# Goldfish_BigBoard_2.net
KiCad netlist of a schematic drawn in EAGLE
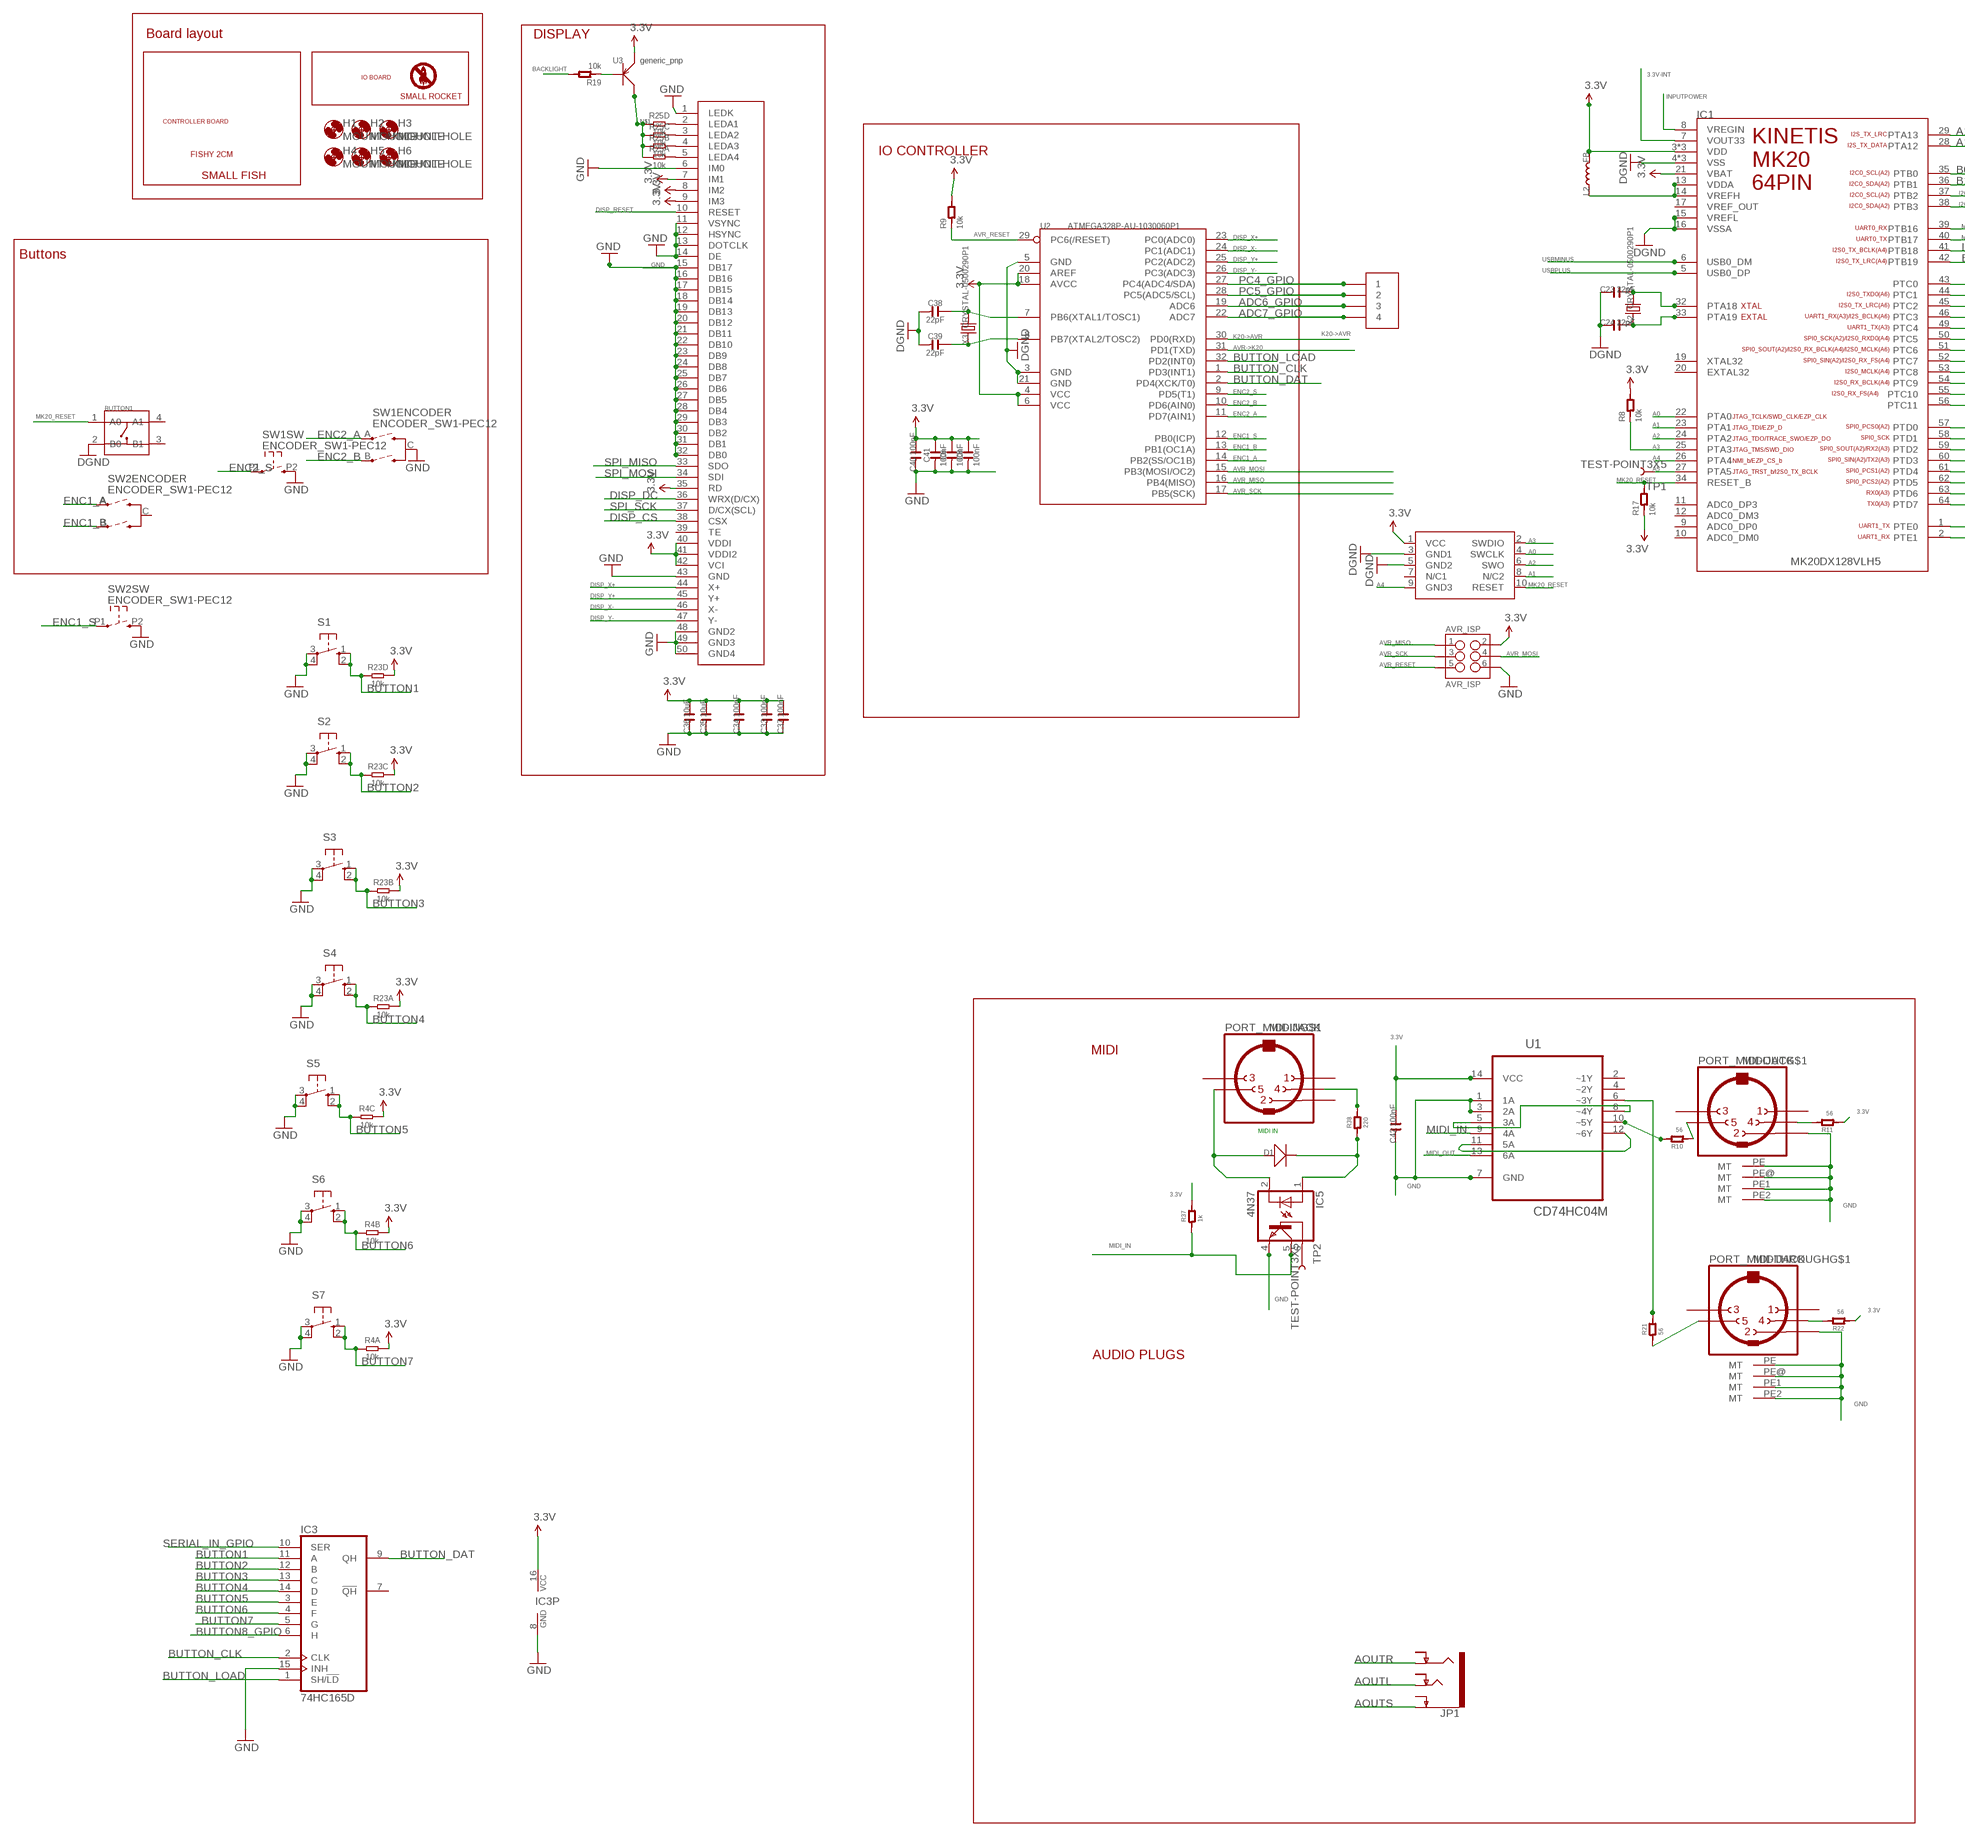
[diagram p0: schematic, sheet 1, part 1 of 3]
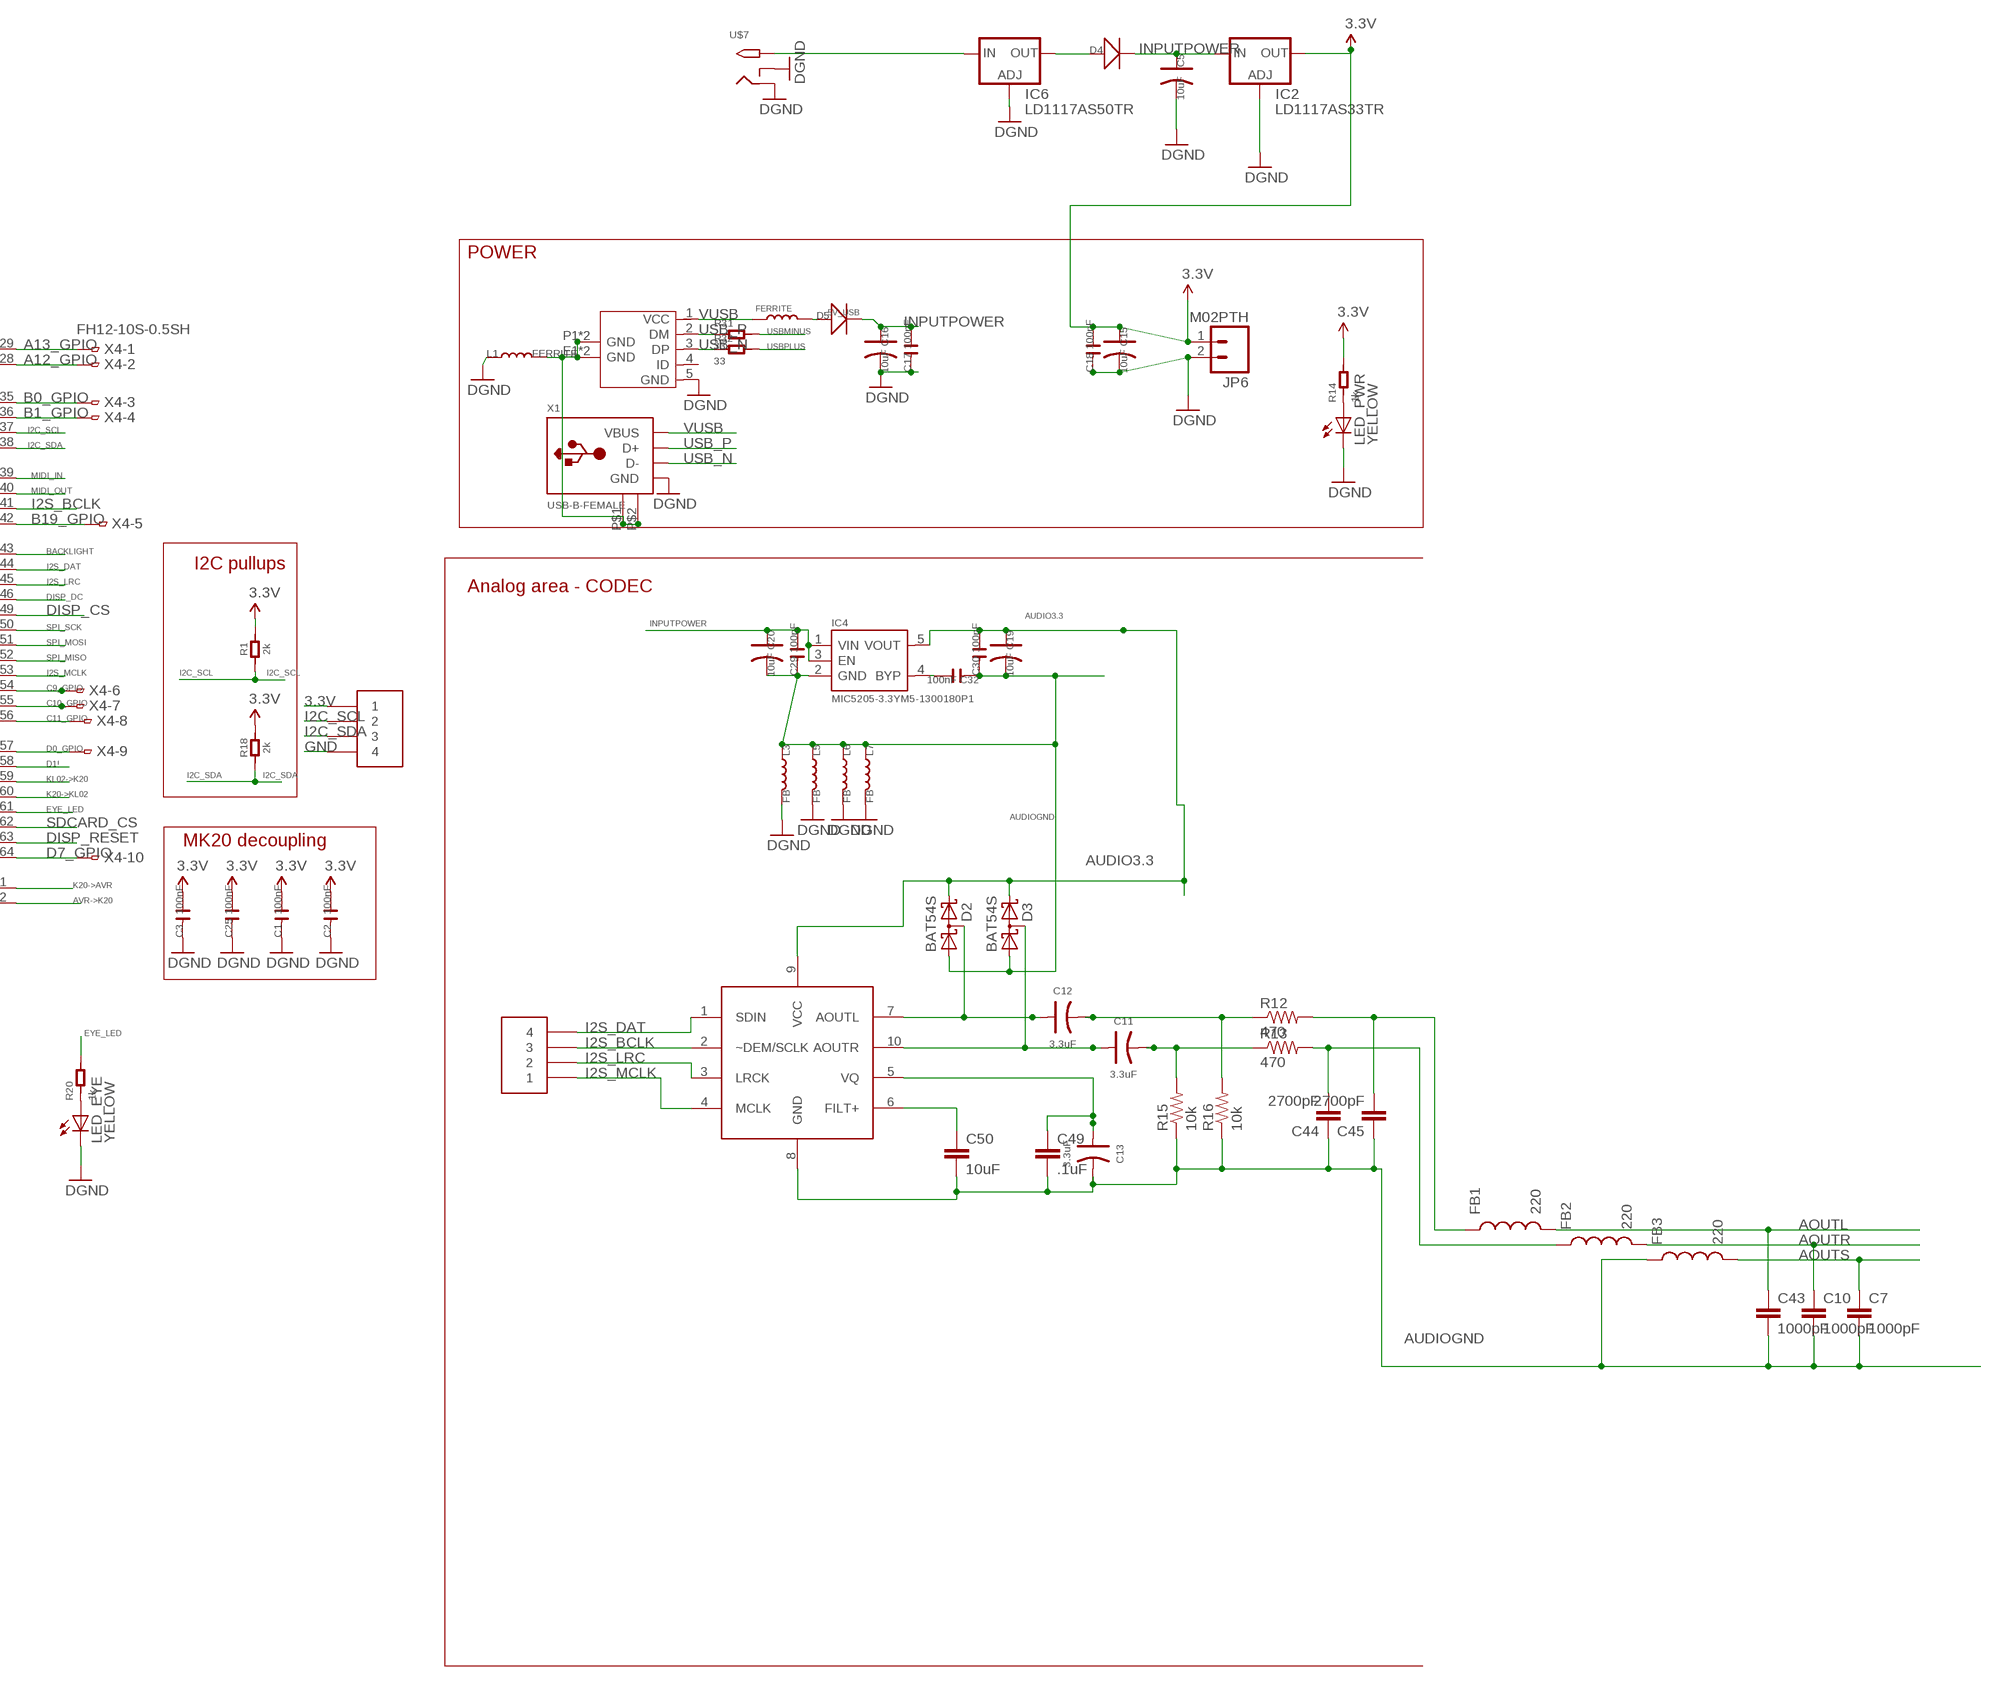
[diagram p1: schematic, sheet 1, part 2 of 3]
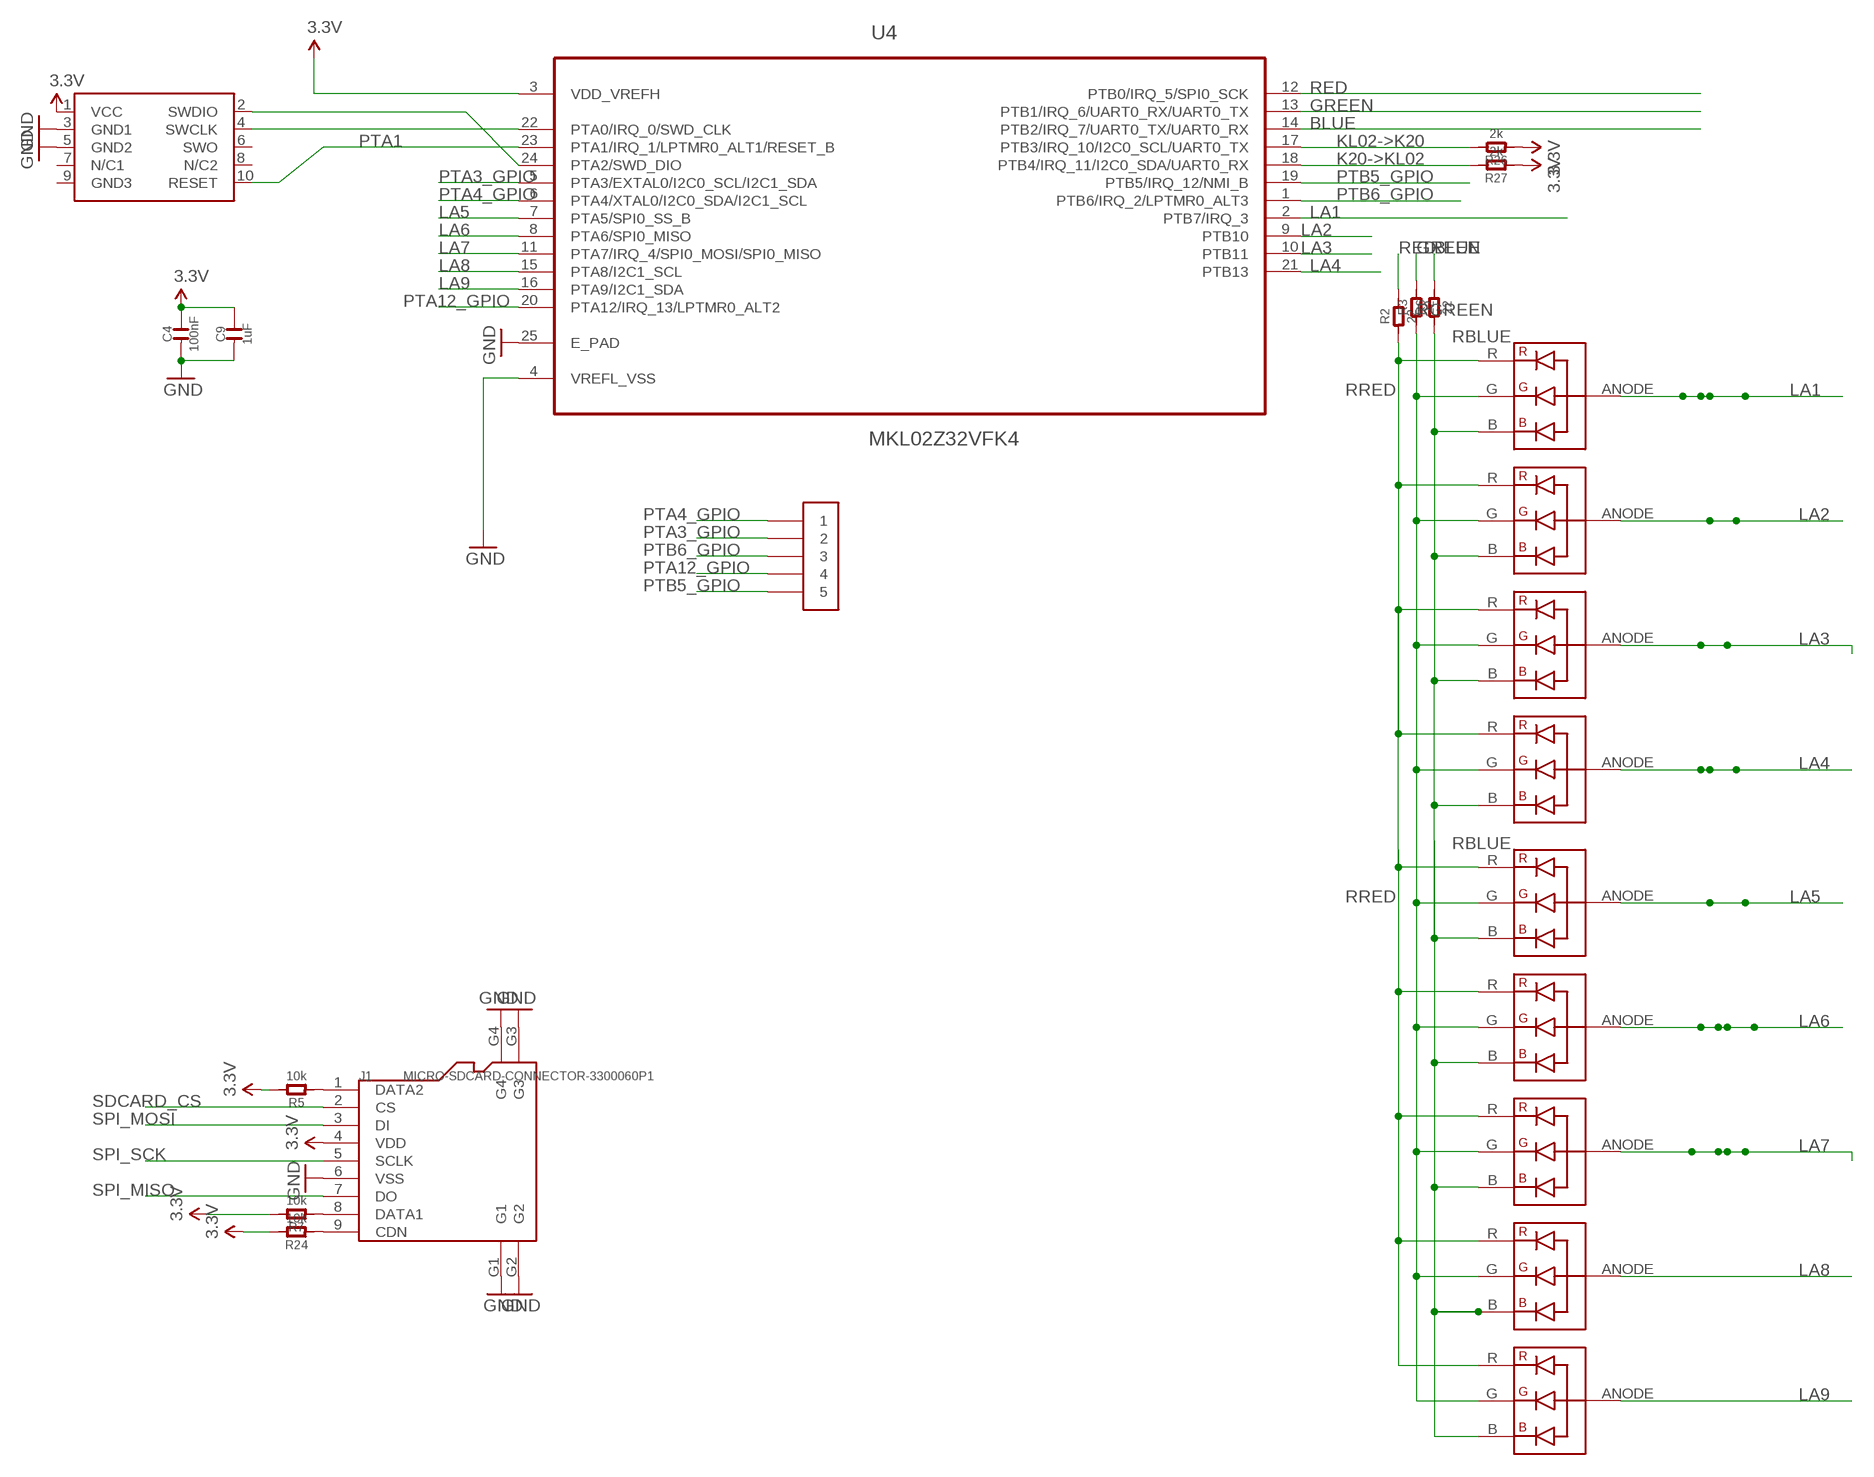
[diagram p2: schematic, sheet 1, part 3 of 3]

(export (version "E")
  (design (tool "Eeschema 10.0.6"))
  (components
    (comp (ref "AVR_ISP")
      (value "AVR_ISP")
      (footprint "eagle-import:2X3_SMT_POSTS")
      (libsource (lib "eagle-import") (part "M03X2SMT"))
    )
    (comp (ref "BUTTON1")
      (value "BUTTON-4P-3100010P1")
      (footprint "eagle-import:4P-SMD-6.0X6.0X5.0H")
      (libsource (lib "eagle-import") (part "BUTTON-4P-3100010P1"))
    )
    (comp (ref "C1")
      (value "100nF")
      (footprint "eagle-import:C0603")
      (libsource (lib "eagle-import") (part "OPL Eagle Library_C-0603"))
    )
    (comp (ref "C2")
      (value "100nF")
      (footprint "eagle-import:C0603")
      (libsource (lib "eagle-import") (part "OPL Eagle Library_C-0603"))
    )
    (comp (ref "C3")
      (value "100nF")
      (footprint "eagle-import:C0603")
      (libsource (lib "eagle-import") (part "OPL Eagle Library_C-0603"))
    )
    (comp (ref "C4")
      (value "100nF")
      (footprint "eagle-import:C0603")
      (libsource (lib "eagle-import") (part "C-0603"))
    )
    (comp (ref "C5")
      (value "10uF")
      (footprint "eagle-import:AVX-A")
      (libsource (lib "eagle-import") (part "OPL Eagle Library_C-POLAR-A"))
    )
    (comp (ref "C6")
      (value "100nF")
      (footprint "eagle-import:C0603")
      (libsource (lib "eagle-import") (part "C-0603"))
    )
    (comp (ref "C7")
      (value "1000pF")
      (footprint "eagle-import:0402-CAP")
      (libsource (lib "eagle-import") (part "CAP0402-CAP"))
    )
    (comp (ref "C8")
      (value "100nF")
      (footprint "eagle-import:C0603")
      (libsource (lib "eagle-import") (part "C-0603"))
    )
    (comp (ref "C9")
      (value "1uF")
      (footprint "eagle-import:C0603")
      (libsource (lib "eagle-import") (part "C-0603"))
    )
    (comp (ref "C10")
      (value "1000pF")
      (footprint "eagle-import:0402-CAP")
      (libsource (lib "eagle-import") (part "CAP0402-CAP"))
    )
    (comp (ref "C11")
      (value "3.3uF")
      (footprint "eagle-import:AVX-A")
      (libsource (lib "eagle-import") (part "C-POLAR-A"))
    )
    (comp (ref "C12")
      (value "3.3uF")
      (footprint "eagle-import:AVX-A")
      (libsource (lib "eagle-import") (part "C-POLAR-A"))
    )
    (comp (ref "C13")
      (value "3.3uF")
      (footprint "eagle-import:AVX-A")
      (libsource (lib "eagle-import") (part "C-POLAR-A"))
    )
    (comp (ref "C15")
      (value "10uF")
      (footprint "eagle-import:AVX-A")
      (libsource (lib "eagle-import") (part "OPL Eagle Library_C-POLAR-A"))
    )
    (comp (ref "C16")
      (value "10uF")
      (footprint "eagle-import:AVX-A")
      (libsource (lib "eagle-import") (part "OPL Eagle Library_C-POLAR-A"))
    )
    (comp (ref "C17")
      (value "100nF")
      (footprint "eagle-import:C0603")
      (libsource (lib "eagle-import") (part "OPL Eagle Library_C-0603"))
    )
    (comp (ref "C18")
      (value "100nF")
      (footprint "eagle-import:C0603")
      (libsource (lib "eagle-import") (part "OPL Eagle Library_C-0603"))
    )
    (comp (ref "C19")
      (value "10uF")
      (footprint "eagle-import:AVX-A")
      (libsource (lib "eagle-import") (part "OPL Eagle Library_C-POLAR-A"))
    )
    (comp (ref "C20")
      (value "10uF")
      (footprint "eagle-import:AVX-A")
      (libsource (lib "eagle-import") (part "OPL Eagle Library_C-POLAR-A"))
    )
    (comp (ref "C23")
      (value "22pF")
      (footprint "eagle-import:C0603")
      (libsource (lib "eagle-import") (part "OPL Eagle Library_C-0603"))
    )
    (comp (ref "C24")
      (value "22pF")
      (footprint "eagle-import:C0603")
      (libsource (lib "eagle-import") (part "OPL Eagle Library_C-0603"))
    )
    (comp (ref "C25")
      (value "100nF")
      (footprint "eagle-import:C0603")
      (libsource (lib "eagle-import") (part "OPL Eagle Library_C-0603"))
    )
    (comp (ref "C29")
      (value "100nF")
      (footprint "eagle-import:C0603")
      (libsource (lib "eagle-import") (part "OPL Eagle Library_C-0603"))
    )
    (comp (ref "C30")
      (value "100nF")
      (footprint "eagle-import:C0603")
      (libsource (lib "eagle-import") (part "OPL Eagle Library_C-0603"))
    )
    (comp (ref "C32")
      (value "100nF")
      (footprint "eagle-import:C0603")
      (libsource (lib "eagle-import") (part "OPL Eagle Library_C-0603"))
    )
    (comp (ref "C33")
      (value "100nF")
      (footprint "eagle-import:C0603")
      (libsource (lib "eagle-import") (part "OPL Eagle Library_C-0603"))
    )
    (comp (ref "C34")
      (value "100nF")
      (footprint "eagle-import:C0603")
      (libsource (lib "eagle-import") (part "OPL Eagle Library_C-0603"))
    )
    (comp (ref "C35")
      (value "10uF")
      (footprint "eagle-import:C0603")
      (libsource (lib "eagle-import") (part "OPL Eagle Library_C-0603"))
    )
    (comp (ref "C36")
      (value "10uF")
      (footprint "eagle-import:C0805")
      (libsource (lib "eagle-import") (part "OPL Eagle Library_C-0805"))
    )
    (comp (ref "C37")
      (value "100nF")
      (footprint "eagle-import:C0805")
      (libsource (lib "eagle-import") (part "OPL Eagle Library_C-0805"))
    )
    (comp (ref "C38")
      (value "22pF")
      (footprint "eagle-import:C0603")
      (libsource (lib "eagle-import") (part "C-0603"))
    )
    (comp (ref "C39")
      (value "22pF")
      (footprint "eagle-import:C0603")
      (libsource (lib "eagle-import") (part "C-0603"))
    )
    (comp (ref "C40")
      (value "100nF")
      (footprint "eagle-import:C0603")
      (libsource (lib "eagle-import") (part "OPL Eagle Library_C-0603"))
    )
    (comp (ref "C41")
      (value "100nF")
      (footprint "eagle-import:C0603")
      (libsource (lib "eagle-import") (part "C-0603"))
    )
    (comp (ref "C42")
      (value "100nF")
      (footprint "eagle-import:C0603")
      (libsource (lib "eagle-import") (part "OPL Eagle Library_C-0603"))
    )
    (comp (ref "C43")
      (value "1000pF")
      (footprint "eagle-import:0402-CAP")
      (libsource (lib "eagle-import") (part "CAP0402-CAP"))
    )
    (comp (ref "C44")
      (value "2700pF")
      (footprint "eagle-import:0402-CAP")
      (libsource (lib "eagle-import") (part "CAP0402-CAP"))
    )
    (comp (ref "C45")
      (value "2700pF")
      (footprint "eagle-import:0402-CAP")
      (libsource (lib "eagle-import") (part "CAP0402-CAP"))
    )
    (comp (ref "C49")
      (value ".1uF")
      (footprint "eagle-import:0402-CAP")
      (libsource (lib "eagle-import") (part "CAP0402-CAP"))
    )
    (comp (ref "C50")
      (value "10uF")
      (footprint "eagle-import:0402-CAP")
      (libsource (lib "eagle-import") (part "CAP0402-CAP"))
    )
    (comp (ref "D1")
      (value "D-D1206")
      (footprint "eagle-import:LL-34")
      (libsource (lib "eagle-import") (part "D-D1206"))
    )
    (comp (ref "D2")
      (value "BAT54S")
      (footprint "eagle-import:SOT23")
      (libsource (lib "eagle-import") (part "BAT54S"))
    )
    (comp (ref "D3")
      (value "BAT54S")
      (footprint "eagle-import:SOT23")
      (libsource (lib "eagle-import") (part "BAT54S"))
    )
    (comp (ref "D4")
      (value "D-D1206")
      (footprint "eagle-import:LL-34")
      (libsource (lib "eagle-import") (part "D-D1206"))
    )
    (comp (ref "D5")
      (value "D-D1206")
      (footprint "eagle-import:LL-34")
      (libsource (lib "eagle-import") (part "D-D1206"))
    )
    (comp (ref "FB1")
      (value "220")
      (footprint "eagle-import:0805")
      (libsource (lib "eagle-import") (part "INDUCTOR0805"))
    )
    (comp (ref "FB2")
      (value "220")
      (footprint "eagle-import:0805")
      (libsource (lib "eagle-import") (part "INDUCTOR0805"))
    )
    (comp (ref "FB3")
      (value "220")
      (footprint "eagle-import:0805")
      (libsource (lib "eagle-import") (part "INDUCTOR0805"))
    )
    (comp (ref "H1")
      (value "MOUNT-HOLE")
      (footprint "eagle-import:3.2-NOMARKINGS-SMALLSAFEZONE")
      (libsource (lib "eagle-import") (part "MOUNT-HOLE"))
    )
    (comp (ref "H2")
      (value "MOUNT-HOLE")
      (footprint "eagle-import:3.2-NOMARKINGS-SMALLSAFEZONE")
      (libsource (lib "eagle-import") (part "MOUNT-HOLE"))
    )
    (comp (ref "H3")
      (value "MOUNT-HOLE")
      (footprint "eagle-import:3.2-NOMARKINGS-SMALLSAFEZONE")
      (libsource (lib "eagle-import") (part "MOUNT-HOLE"))
    )
    (comp (ref "H4")
      (value "MOUNT-HOLE")
      (footprint "eagle-import:3.2-NOMARKINGS-SMALLSAFEZONE")
      (libsource (lib "eagle-import") (part "MOUNT-HOLE"))
    )
    (comp (ref "H5")
      (value "MOUNT-HOLE")
      (footprint "eagle-import:3.2-NOMARKINGS-SMALLSAFEZONE")
      (libsource (lib "eagle-import") (part "MOUNT-HOLE"))
    )
    (comp (ref "H6")
      (value "MOUNT-HOLE")
      (footprint "eagle-import:3.2-NOMARKINGS-SMALLSAFEZONE")
      (libsource (lib "eagle-import") (part "MOUNT-HOLE"))
    )
    (comp (ref "IC1")
      (value "MK20DX128VLH5")
      (footprint "eagle-import:MK20DX128VLH5")
      (libsource (lib "eagle-import") (part "MK20DX128VLH5"))
    )
    (comp (ref "IC2")
      (value "LD1117AS33TR")
      (footprint "eagle-import:SOT223")
      (libsource (lib "eagle-import") (part "LD1117A?S33TR"))
    )
    (comp (ref "IC3")
      (value "74HC165D")
      (footprint "eagle-import:SO16")
      (libsource (lib "eagle-import") (part "74165DHC"))
    )
    (comp (ref "IC4")
      (value "MIC5205-3.3YM5-1300180P1")
      (footprint "eagle-import:SOT23-5")
      (libsource (lib "eagle-import") (part "MIC5205-3.3YM5-1300180P1"))
    )
    (comp (ref "IC5")
      (value "4N37")
      (footprint "eagle-import:DIL06")
      (fields (field (name "MF") "FAIRCHILD SEMICONDUCTOR"))
      (libsource (lib "eagle-import") (part "4N37"))
    )
    (comp (ref "IC6")
      (value "LD1117AS50TR")
      (footprint "eagle-import:SOT223")
      (libsource (lib "eagle-import") (part "LD1117A?S50TR"))
    )
    (comp (ref "J1")
      (value "MICRO-SDCARD-CONNECTOR-3300060P1")
      (footprint "eagle-import:9P-SMD-W-RING")
      (libsource (lib "eagle-import") (part "MICRO-SDCARD-CONNECTOR-3300060P1"))
    )
    (comp (ref "J2")
      (value "MICRO-USB-5P-340015001")
      (footprint "eagle-import:B-SMD-5P")
      (libsource (lib "eagle-import") (part "MICRO-USB-5P-340015001"))
    )
    (comp (ref "JP1")
      (value "AUDIO-JACK4-.25-HORIZ-TRS")
      (footprint "eagle-import:AUDIO-JACK-.25-INCH-HORIZ-PTH")
      (libsource (lib "eagle-import") (part "AUDIO-JACK4-.25-HORIZ-TRS"))
    )
    (comp (ref "JP6")
      (value "M02PTH")
      (footprint "eagle-import:1X02")
      (libsource (lib "eagle-import") (part "M02PTH"))
    )
    (comp (ref "L1")
      (value "FERRITE")
      (footprint "eagle-import:L0603")
      (libsource (lib "eagle-import") (part "L-0603"))
    )
    (comp (ref "L2")
      (value "FB")
      (footprint "eagle-import:L0603")
      (libsource (lib "eagle-import") (part "L-0603"))
    )
    (comp (ref "L3")
      (value "FB")
      (footprint "eagle-import:L0603")
      (libsource (lib "eagle-import") (part "L-0603"))
    )
    (comp (ref "L4")
      (value "FERRITE")
      (footprint "eagle-import:L0603")
      (libsource (lib "eagle-import") (part "L-0603"))
    )
    (comp (ref "L5")
      (value "FB")
      (footprint "eagle-import:L0603")
      (libsource (lib "eagle-import") (part "L-0603"))
    )
    (comp (ref "L6")
      (value "FB")
      (footprint "eagle-import:L0603")
      (libsource (lib "eagle-import") (part "L-0603"))
    )
    (comp (ref "L7")
      (value "FB")
      (footprint "eagle-import:L0603")
      (libsource (lib "eagle-import") (part "L-0603"))
    )
    (comp (ref "LED_EYE")
      (value "YELLOW")
      (footprint "eagle-import:CHIP-LED0603")
      (libsource (lib "eagle-import") (part "LEDCHIP-LED0603"))
    )
    (comp (ref "LED_PWR")
      (value "YELLOW")
      (footprint "eagle-import:CHIP-LED0603")
      (libsource (lib "eagle-import") (part "LEDCHIP-LED0603"))
    )
    (comp (ref "PORT_MIDI-IN")
      (value "MIDIJACK")
      (footprint "eagle-import:CP-2350")
      (libsource (lib "eagle-import") (part "MIDIJACK"))
    )
    (comp (ref "PORT_MIDI-OUT")
      (value "MIDIJACK")
      (footprint "eagle-import:CP-2350")
      (libsource (lib "eagle-import") (part "MIDIJACK"))
    )
    (comp (ref "PORT_MIDI-THROUGH")
      (value "MIDIJACK")
      (footprint "eagle-import:CP-2350")
      (libsource (lib "eagle-import") (part "MIDIJACK"))
    )
    (comp (ref "R1")
      (value "2k")
      (footprint "eagle-import:R0603")
      (libsource (lib "eagle-import") (part "R-0603"))
    )
    (comp (ref "R2")
      (value "22")
      (footprint "eagle-import:R0603")
      (libsource (lib "eagle-import") (part "R-0603"))
    )
    (comp (ref "R3")
      (value "22")
      (footprint "eagle-import:R0603")
      (libsource (lib "eagle-import") (part "R-0603"))
    )
    (comp (ref "R4")
      (value "10k")
      (footprint "eagle-import:R1206-8")
      (libsource (lib "eagle-import") (part "R-4R"))
    )
    (comp (ref "R5")
      (value "10k")
      (footprint "eagle-import:R0603")
      (libsource (lib "eagle-import") (part "R-0603"))
    )
    (comp (ref "R6")
      (value "22")
      (footprint "eagle-import:R0603")
      (libsource (lib "eagle-import") (part "R-0603"))
    )
    (comp (ref "R7")
      (value "10k")
      (footprint "eagle-import:R0603")
      (libsource (lib "eagle-import") (part "R-0603"))
    )
    (comp (ref "R8")
      (value "10k")
      (footprint "eagle-import:R0603")
      (libsource (lib "eagle-import") (part "OPL Eagle Library_R-0603"))
    )
    (comp (ref "R9")
      (value "10k")
      (footprint "eagle-import:R0603")
      (libsource (lib "eagle-import") (part "OPL Eagle Library_R-0603"))
    )
    (comp (ref "R10")
      (value "56")
      (footprint "eagle-import:R0603")
      (libsource (lib "eagle-import") (part "OPL Eagle Library_R-0603"))
    )
    (comp (ref "R11")
      (value "56")
      (footprint "eagle-import:R0603")
      (libsource (lib "eagle-import") (part "OPL Eagle Library_R-0603"))
    )
    (comp (ref "R12")
      (value "470")
      (footprint "eagle-import:0603-RES")
      (libsource (lib "eagle-import") (part "RESISTOR0603-RES"))
    )
    (comp (ref "R13")
      (value "470")
      (footprint "eagle-import:0603-RES")
      (libsource (lib "eagle-import") (part "RESISTOR0603-RES"))
    )
    (comp (ref "R14")
      (value "1k")
      (footprint "eagle-import:R0603")
      (libsource (lib "eagle-import") (part "OPL Eagle Library_R-0603"))
    )
    (comp (ref "R15")
      (value "10k")
      (footprint "eagle-import:0603-RES")
      (libsource (lib "eagle-import") (part "RESISTOR0603-RES"))
    )
    (comp (ref "R16")
      (value "10k")
      (footprint "eagle-import:0603-RES")
      (libsource (lib "eagle-import") (part "RESISTOR0603-RES"))
    )
    (comp (ref "R17")
      (value "10k")
      (footprint "eagle-import:R0603")
      (libsource (lib "eagle-import") (part "OPL Eagle Library_R-0603"))
    )
    (comp (ref "R18")
      (value "2k")
      (footprint "eagle-import:R0603")
      (libsource (lib "eagle-import") (part "R-0603"))
    )
    (comp (ref "R19")
      (value "10k")
      (footprint "eagle-import:R0603")
      (libsource (lib "eagle-import") (part "OPL Eagle Library_R-0603"))
    )
    (comp (ref "R20")
      (value "1k")
      (footprint "eagle-import:R0603")
      (libsource (lib "eagle-import") (part "OPL Eagle Library_R-0603"))
    )
    (comp (ref "R21")
      (value "56")
      (footprint "eagle-import:R0603")
      (libsource (lib "eagle-import") (part "OPL Eagle Library_R-0603"))
    )
    (comp (ref "R22")
      (value "56")
      (footprint "eagle-import:R0603")
      (libsource (lib "eagle-import") (part "OPL Eagle Library_R-0603"))
    )
    (comp (ref "R23")
      (value "10k")
      (footprint "eagle-import:R1206-8")
      (libsource (lib "eagle-import") (part "R-4R"))
    )
    (comp (ref "R24")
      (value "10k")
      (footprint "eagle-import:R0603")
      (libsource (lib "eagle-import") (part "R-0603"))
    )
    (comp (ref "R25")
      (value "10k")
      (footprint "eagle-import:R1206-8")
      (libsource (lib "eagle-import") (part "R-4R"))
    )
    (comp (ref "R26")
      (value "2k")
      (footprint "eagle-import:R0603")
      (libsource (lib "eagle-import") (part "R-0603"))
    )
    (comp (ref "R27")
      (value "2k")
      (footprint "eagle-import:R0603")
      (libsource (lib "eagle-import") (part "R-0603"))
    )
    (comp (ref "R31")
      (value "33")
      (footprint "eagle-import:R0603")
      (libsource (lib "eagle-import") (part "OPL Eagle Library_R-0603"))
    )
    (comp (ref "R32")
      (value "33")
      (footprint "eagle-import:R0603")
      (libsource (lib "eagle-import") (part "OPL Eagle Library_R-0603"))
    )
    (comp (ref "R37")
      (value "1k")
      (footprint "eagle-import:R0603")
      (libsource (lib "eagle-import") (part "OPL Eagle Library_R-0603"))
    )
    (comp (ref "R38")
      (value "220")
      (footprint "eagle-import:R0603")
      (libsource (lib "eagle-import") (part "OPL Eagle Library_R-0603"))
    )
    (comp (ref "S1")
      (value "40-XX-ROUND")
      (footprint "eagle-import:B3F-40XX-ROUND")
      (libsource (lib "eagle-import") (part "40-XX-ROUND"))
    )
    (comp (ref "S2")
      (value "40-XX-ROUND")
      (footprint "eagle-import:B3F-40XX-ROUND")
      (libsource (lib "eagle-import") (part "40-XX-ROUND"))
    )
    (comp (ref "S3")
      (value "40-XX-ROUND")
      (footprint "eagle-import:B3F-40XX-ROUND")
      (libsource (lib "eagle-import") (part "40-XX-ROUND"))
    )
    (comp (ref "S4")
      (value "40-XX-ROUND")
      (footprint "eagle-import:B3F-40XX-ROUND")
      (libsource (lib "eagle-import") (part "40-XX-ROUND"))
    )
    (comp (ref "S5")
      (value "40-XX-ROUND")
      (footprint "eagle-import:B3F-40XX-ROUND")
      (libsource (lib "eagle-import") (part "40-XX-ROUND"))
    )
    (comp (ref "S6")
      (value "40-XX-ROUND")
      (footprint "eagle-import:B3F-40XX-ROUND")
      (libsource (lib "eagle-import") (part "40-XX-ROUND"))
    )
    (comp (ref "S7")
      (value "40-XX-ROUND")
      (footprint "eagle-import:B3F-40XX-ROUND")
      (libsource (lib "eagle-import") (part "40-XX-ROUND"))
    )
    (comp (ref "SW1")
      (value "ENCODER_SW1-PEC12")
      (footprint "eagle-import:PEC12_INCREMENTAL_ENCODER")
      (libsource (lib "eagle-import") (part "ENCODER_SW1-PEC12"))
    )
    (comp (ref "SW2")
      (value "ENCODER_SW1-PEC12")
      (footprint "eagle-import:PEC12_INCREMENTAL_ENCODER")
      (libsource (lib "eagle-import") (part "ENCODER_SW1-PEC12"))
    )
    (comp (ref "SWD1")
      (value "CORTEX_SWD")
      (footprint "eagle-import:M50-3600542")
      (libsource (lib "eagle-import") (part "CORTEX_SWD"))
    )
    (comp (ref "SWD2")
      (value "CORTEX_SWD")
      (footprint "eagle-import:M50-3600542")
      (libsource (lib "eagle-import") (part "CORTEX_SWD"))
    )
    (comp (ref "TP1")
      (value "TEST-POINT3X5")
      (footprint "eagle-import:PAD.03X.05")
      (libsource (lib "eagle-import") (part "TEST-POINT3X5"))
    )
    (comp (ref "TP2")
      (value "TEST-POINT3X5")
      (footprint "eagle-import:PAD.03X.05")
      (libsource (lib "eagle-import") (part "TEST-POINT3X5"))
    )
    (comp (ref "U$1")
      (value "2.8\"TFT2.8\"TFT")
      (footprint "eagle-import:2.8_TFT")
      (libsource (lib "eagle-import") (part "2.8{dblquote}TFT2.8{dblquote}TFT"))
    )
    (comp (ref "U$3")
      (value "FISH2CM_SILK")
      (footprint "eagle-import:FISH_WITHSILK")
      (libsource (lib "eagle-import") (part "FISH2CM_SILK"))
    )
    (comp (ref "U$4")
      (value "FISH_SMALL")
      (footprint "eagle-import:FISH_SMALL")
      (libsource (lib "eagle-import") (part "FISH_SMALL"))
    )
    (comp (ref "U$6")
      (value "CS4344-DAC")
      (footprint "eagle-import:TSSOP-10")
      (libsource (lib "eagle-import") (part "CS4344-DAC"))
    )
    (comp (ref "U$7")
      (value "2.1MMJACKTHM")
      (footprint "eagle-import:163-179PH-EX")
      (libsource (lib "eagle-import") (part "2.1MMJACKTHM"))
    )
    (comp (ref "U$8")
      (value "SMALLROCKET")
      (footprint "eagle-import:SMALLROCKET")
      (libsource (lib "eagle-import") (part "SMALLROCKET"))
    )
    (comp (ref "U$9")
      (value "RGBLED_COMMONANODE")
      (footprint "eagle-import:3.5X2.8_RGB_LED")
      (libsource (lib "eagle-import") (part "RGBLED_COMMONANODE"))
    )
    (comp (ref "U$10")
      (value "RGBLED_COMMONANODE")
      (footprint "eagle-import:3.5X2.8_RGB_LED")
      (libsource (lib "eagle-import") (part "RGBLED_COMMONANODE"))
    )
    (comp (ref "U$11")
      (value "M05")
      (footprint "eagle-import:M05")
      (libsource (lib "eagle-import") (part "M05"))
    )
    (comp (ref "U$12")
      (value "RGBLED_COMMONANODE")
      (footprint "eagle-import:3.5X2.8_RGB_LED")
      (libsource (lib "eagle-import") (part "RGBLED_COMMONANODE"))
    )
    (comp (ref "U$13")
      (value "RGBLED_COMMONANODE")
      (footprint "eagle-import:3.5X2.8_RGB_LED")
      (libsource (lib "eagle-import") (part "RGBLED_COMMONANODE"))
    )
    (comp (ref "U$14")
      (value "RGBLED_COMMONANODE")
      (footprint "eagle-import:3.5X2.8_RGB_LED")
      (libsource (lib "eagle-import") (part "RGBLED_COMMONANODE"))
    )
    (comp (ref "U$15")
      (value "RGBLED_COMMONANODE")
      (footprint "eagle-import:3.5X2.8_RGB_LED")
      (libsource (lib "eagle-import") (part "RGBLED_COMMONANODE"))
    )
    (comp (ref "U$16")
      (value "RGBLED_COMMONANODE")
      (footprint "eagle-import:3.5X2.8_RGB_LED")
      (libsource (lib "eagle-import") (part "RGBLED_COMMONANODE"))
    )
    (comp (ref "U$17")
      (value "RGBLED_COMMONANODE")
      (footprint "eagle-import:3.5X2.8_RGB_LED")
      (libsource (lib "eagle-import") (part "RGBLED_COMMONANODE"))
    )
    (comp (ref "U$18")
      (value "RGBLED_COMMONANODE")
      (footprint "eagle-import:3.5X2.8_RGB_LED")
      (libsource (lib "eagle-import") (part "RGBLED_COMMONANODE"))
    )
    (comp (ref "U$20")
      (value "M04")
      (footprint "eagle-import:M04")
      (libsource (lib "eagle-import") (part "M04"))
    )
    (comp (ref "U$21")
      (value "M04")
      (footprint "eagle-import:M04")
      (libsource (lib "eagle-import") (part "M04"))
    )
    (comp (ref "U$22")
      (value "M04")
      (footprint "eagle-import:M04")
      (libsource (lib "eagle-import") (part "M04"))
    )
    (comp (ref "U1")
      (value "CD74HC04M")
      (footprint "eagle-import:SOIC127P600X175-14N")
      (libsource (lib "eagle-import") (part "CD74HC04M"))
    )
    (comp (ref "U2")
      (value "ATMEGA328P-AU-1030060P1")
      (footprint "eagle-import:TQFP32")
      (libsource (lib "eagle-import") (part "ATMEGA328P-AU-1030060P1"))
    )
    (comp (ref "U3")
      (value "generic_pnp")
      (footprint "eagle-import:SOT23")
      (libsource (lib "eagle-import") (part "TRANSISTOR-PNP-041003001"))
    )
    (comp (ref "U4")
      (value "MKL02Z32VFK4")
      (footprint "eagle-import:QFN50P400X400X100-25N")
      (libsource (lib "eagle-import") (part "MKL02Z32VFK4"))
    )
    (comp (ref "X1")
      (value "USB-B-FEMALE")
      (footprint "eagle-import:FCI61729")
      (libsource (lib "eagle-import") (part "USB-B-FEMALE"))
    )
    (comp (ref "X2")
      (value "CRYSTAL-0500290P1")
      (footprint "eagle-import:2P-SMD-5.0X3.2")
      (libsource (lib "eagle-import") (part "OPL Eagle Library_CRYSTAL-0500290P1"))
    )
    (comp (ref "X3")
      (value "CRYSTAL-0500290P1")
      (footprint "eagle-import:2P-SMD-5.0X3.2")
      (libsource (lib "eagle-import") (part "CRYSTAL-0500290P1"))
    )
    (comp (ref "X4")
      (value "FH12-10S-0.5SH")
      (footprint "eagle-import:FH12-10S-0.5SH")
      (fields (field (name "MPN") "FH12-10S-0.5SH(55)"))
      (libsource (lib "eagle-import") (part "FH12-10S-0.5SH"))
    )
  )
  (nets
    (net (code "1") (name "/3.3V-INT") (class "Default")
      (node (ref "IC1") (pin "7") (pinfunction "VOUT33_7") (pintype "bidirectional"))
    )
    (net (code "2") (name "/5V_USB") (class "Default")
      (node (ref "D5") (pin "A") (pinfunction "+_A") (pintype "passive"))
      (node (ref "L4") (pin "2") (pinfunction "2_2") (pintype "passive"))
    )
    (net (code "3") (name "/A0") (class "Default")
      (node (ref "IC1") (pin "22") (pinfunction "PTA0_22") (pintype "bidirectional"))
      (node (ref "SWD1") (pin "4") (pinfunction "SWCLK_4") (pintype "bidirectional"))
    )
    (net (code "4") (name "/A1") (class "Default")
      (node (ref "IC1") (pin "23") (pinfunction "PTA1_23") (pintype "bidirectional"))
      (node (ref "SWD1") (pin "8") (pinfunction "N/C2_8") (pintype "bidirectional"))
    )
    (net (code "5") (name "/A2") (class "Default")
      (node (ref "IC1") (pin "24") (pinfunction "PTA2_24") (pintype "bidirectional"))
      (node (ref "SWD1") (pin "6") (pinfunction "SWO_6") (pintype "bidirectional"))
    )
    (net (code "6") (name "/A3") (class "Default")
      (node (ref "IC1") (pin "25") (pinfunction "PTA3_25") (pintype "bidirectional"))
      (node (ref "R8") (pin "1") (pinfunction "1_1") (pintype "bidirectional"))
      (node (ref "SWD1") (pin "2") (pinfunction "SWDIO_2") (pintype "bidirectional"))
    )
    (net (code "7") (name "/A4") (class "Default")
      (node (ref "IC1") (pin "26") (pinfunction "PTA4_26") (pintype "bidirectional"))
      (node (ref "SWD1") (pin "9") (pinfunction "GND3_9") (pintype "bidirectional"))
    )
    (net (code "8") (name "/A5") (class "Default")
      (node (ref "IC1") (pin "27") (pinfunction "PTA5_27") (pintype "bidirectional"))
      (node (ref "TP1") (pin "P$1") (pinfunction "1_P$1") (pintype "bidirectional"))
    )
    (net (code "9") (name "/A12_GPIO") (class "Default")
      (node (ref "IC1") (pin "28") (pinfunction "PTA12_28") (pintype "bidirectional"))
      (node (ref "X4") (pin "2") (pinfunction "1_2") (pintype "passive"))
    )
    (net (code "10") (name "/A13_GPIO") (class "Default")
      (node (ref "IC1") (pin "29") (pinfunction "PTA13_29") (pintype "bidirectional"))
      (node (ref "X4") (pin "1") (pinfunction "1_1") (pintype "passive"))
    )
    (net (code "11") (name "/ADC6_GPIO") (class "Default")
      (node (ref "U$20") (pin "P$3") (pinfunction "3_P$3") (pintype "bidirectional"))
      (node (ref "U2") (pin "19") (pinfunction "ADC6_19") (pintype "bidirectional"))
    )
    (net (code "12") (name "/ADC7_GPIO") (class "Default")
      (node (ref "U$20") (pin "P$4") (pinfunction "4_P$4") (pintype "bidirectional"))
      (node (ref "U2") (pin "22") (pinfunction "ADC7_22") (pintype "bidirectional"))
    )
    (net (code "13") (name "/AOUTL") (class "Default")
      (node (ref "C43") (pin "1") (pinfunction "1_1") (pintype "passive"))
      (node (ref "FB1") (pin "2") (pinfunction "2_2") (pintype "passive"))
      (node (ref "JP1") (pin "P$6") (pinfunction "TIP_P$6") (pintype "bidirectional"))
    )
    (net (code "14") (name "/AOUTR") (class "Default")
      (node (ref "C10") (pin "1") (pinfunction "1_1") (pintype "passive"))
      (node (ref "FB2") (pin "2") (pinfunction "2_2") (pintype "passive"))
      (node (ref "JP1") (pin "P$4") (pinfunction "RING_P$4") (pintype "bidirectional"))
    )
    (net (code "15") (name "/AOUTS") (class "Default")
      (node (ref "C7") (pin "1") (pinfunction "1_1") (pintype "passive"))
      (node (ref "FB3") (pin "2") (pinfunction "2_2") (pintype "passive"))
      (node (ref "JP1") (pin "P$2") (pinfunction "EARTH_P$2") (pintype "bidirectional"))
    )
    (net (code "16") (name "/AUDIO3.3") (class "Default")
      (node (ref "C19") (pin "+") (pinfunction "1_+") (pintype "bidirectional"))
      (node (ref "C30") (pin "2") (pinfunction "2_2") (pintype "bidirectional"))
      (node (ref "D2") (pin "2") (pinfunction "C2_2") (pintype "passive"))
      (node (ref "D3") (pin "2") (pinfunction "C2_2") (pintype "passive"))
      (node (ref "IC4") (pin "5") (pinfunction "VOUT_5") (pintype "bidirectional"))
      (node (ref "U$6") (pin "9") (pinfunction "VCC_9") (pintype "bidirectional"))
    )
    (net (code "17") (name "/AUDIOGND") (class "Default")
      (node (ref "C10") (pin "2") (pinfunction "2_2") (pintype "passive"))
      (node (ref "C13") (pin "-") (pinfunction "2_-") (pintype "bidirectional"))
      (node (ref "C19") (pin "-") (pinfunction "2_-") (pintype "bidirectional"))
      (node (ref "C20") (pin "-") (pinfunction "2_-") (pintype "bidirectional"))
      (node (ref "C29") (pin "1") (pinfunction "1_1") (pintype "bidirectional"))
      (node (ref "C30") (pin "1") (pinfunction "1_1") (pintype "bidirectional"))
      (node (ref "C32") (pin "1") (pinfunction "1_1") (pintype "bidirectional"))
      (node (ref "C43") (pin "2") (pinfunction "2_2") (pintype "passive"))
      (node (ref "C44") (pin "1") (pinfunction "1_1") (pintype "passive"))
      (node (ref "C45") (pin "1") (pinfunction "1_1") (pintype "passive"))
      (node (ref "C49") (pin "2") (pinfunction "2_2") (pintype "passive"))
      (node (ref "C50") (pin "2") (pinfunction "2_2") (pintype "passive"))
      (node (ref "C7") (pin "2") (pinfunction "2_2") (pintype "passive"))
      (node (ref "D2") (pin "1") (pinfunction "A1_1") (pintype "passive"))
      (node (ref "D3") (pin "1") (pinfunction "A1_1") (pintype "passive"))
      (node (ref "FB3") (pin "1") (pinfunction "1_1") (pintype "passive"))
      (node (ref "IC4") (pin "2") (pinfunction "GND_2") (pintype "bidirectional"))
      (node (ref "L3") (pin "1") (pinfunction "1_1") (pintype "passive"))
      (node (ref "L5") (pin "1") (pinfunction "1_1") (pintype "passive"))
      (node (ref "L6") (pin "1") (pinfunction "1_1") (pintype "passive"))
      (node (ref "L7") (pin "1") (pinfunction "1_1") (pintype "passive"))
      (node (ref "R15") (pin "1") (pinfunction "1_1") (pintype "passive"))
      (node (ref "R16") (pin "1") (pinfunction "1_1") (pintype "passive"))
      (node (ref "U$6") (pin "8") (pinfunction "GND_8") (pintype "bidirectional"))
    )
    (net (code "18") (name "/AVR->K20") (class "Default")
      (node (ref "IC1") (pin "2") (pinfunction "PTE1_2") (pintype "bidirectional"))
      (node (ref "U2") (pin "31") (pinfunction "PD1(TXD)_31") (pintype "bidirectional"))
    )
    (net (code "19") (name "/AVR_MISO") (class "Default")
      (node (ref "AVR_ISP") (pin "1") (pinfunction "1_1") (pintype "bidirectional"))
      (node (ref "U2") (pin "16") (pinfunction "PB4(MISO)_16") (pintype "bidirectional"))
    )
    (net (code "20") (name "/AVR_MOSI") (class "Default")
      (node (ref "AVR_ISP") (pin "4") (pinfunction "4_4") (pintype "bidirectional"))
      (node (ref "U2") (pin "15") (pinfunction "PB3(MOSI/OC2)_15") (pintype "bidirectional"))
    )
    (net (code "21") (name "/AVR_RESET") (class "Default")
      (node (ref "AVR_ISP") (pin "5") (pinfunction "5_5") (pintype "bidirectional"))
      (node (ref "R9") (pin "1") (pinfunction "1_1") (pintype "bidirectional"))
      (node (ref "U2") (pin "29") (pinfunction "PC6(/RESET)_29") (pintype "bidirectional"))
    )
    (net (code "22") (name "/AVR_SCK") (class "Default")
      (node (ref "AVR_ISP") (pin "3") (pinfunction "3_3") (pintype "bidirectional"))
      (node (ref "U2") (pin "17") (pinfunction "PB5(SCK)_17") (pintype "bidirectional"))
    )
    (net (code "23") (name "/B0_GPIO") (class "Default")
      (node (ref "IC1") (pin "35") (pinfunction "PTB0_35") (pintype "bidirectional"))
      (node (ref "X4") (pin "3") (pinfunction "1_3") (pintype "passive"))
    )
    (net (code "24") (name "/B1_GPIO") (class "Default")
      (node (ref "IC1") (pin "36") (pinfunction "PTB1_36") (pintype "bidirectional"))
      (node (ref "X4") (pin "4") (pinfunction "1_4") (pintype "passive"))
    )
    (net (code "25") (name "/B19_GPIO") (class "Default")
      (node (ref "IC1") (pin "42") (pinfunction "PTB19_42") (pintype "bidirectional"))
      (node (ref "X4") (pin "5") (pinfunction "1_5") (pintype "passive"))
    )
    (net (code "26") (name "/BACKLIGHT") (class "Default")
      (node (ref "IC1") (pin "43") (pinfunction "PTC0_43") (pintype "bidirectional"))
      (node (ref "R19") (pin "2") (pinfunction "2_2") (pintype "bidirectional"))
    )
    (net (code "27") (name "/BLUE") (class "Default")
      (node (ref "R6") (pin "2") (pinfunction "2_2") (pintype "bidirectional"))
      (node (ref "U4") (pin "14") (pinfunction "PTB2/IRQ_7/UART0_TX/UART0_RX_14") (pintype "bidirectional"))
    )
    (net (code "28") (name "/BUTTON1") (class "Default")
      (node (ref "IC3") (pin "11") (pinfunction "A_11") (pintype "input"))
      (node (ref "R23") (pin "4") (pinfunction "1_4") (pintype "passive"))
      (node (ref "S1") (pin "1") (pinfunction "S_1") (pintype "passive"))
      (node (ref "S1") (pin "2") (pinfunction "S1_2") (pintype "passive"))
    )
    (net (code "29") (name "/BUTTON2") (class "Default")
      (node (ref "IC3") (pin "12") (pinfunction "B_12") (pintype "input"))
      (node (ref "R23") (pin "3") (pinfunction "1_3") (pintype "passive"))
      (node (ref "S2") (pin "1") (pinfunction "S_1") (pintype "passive"))
      (node (ref "S2") (pin "2") (pinfunction "S1_2") (pintype "passive"))
    )
    (net (code "30") (name "/BUTTON3") (class "Default")
      (node (ref "IC3") (pin "13") (pinfunction "C_13") (pintype "input"))
      (node (ref "R23") (pin "2") (pinfunction "1_2") (pintype "passive"))
      (node (ref "S3") (pin "1") (pinfunction "S_1") (pintype "passive"))
      (node (ref "S3") (pin "2") (pinfunction "S1_2") (pintype "passive"))
    )
    (net (code "31") (name "/BUTTON4") (class "Default")
      (node (ref "IC3") (pin "14") (pinfunction "D_14") (pintype "input"))
      (node (ref "R23") (pin "1") (pinfunction "1_1") (pintype "passive"))
      (node (ref "S4") (pin "1") (pinfunction "S_1") (pintype "passive"))
      (node (ref "S4") (pin "2") (pinfunction "S1_2") (pintype "passive"))
    )
    (net (code "32") (name "/BUTTON5") (class "Default")
      (node (ref "IC3") (pin "3") (pinfunction "E_3") (pintype "input"))
      (node (ref "R4") (pin "3") (pinfunction "1_3") (pintype "passive"))
      (node (ref "S5") (pin "1") (pinfunction "S_1") (pintype "passive"))
      (node (ref "S5") (pin "2") (pinfunction "S1_2") (pintype "passive"))
    )
    (net (code "33") (name "/BUTTON6") (class "Default")
      (node (ref "IC3") (pin "4") (pinfunction "F_4") (pintype "input"))
      (node (ref "R4") (pin "2") (pinfunction "1_2") (pintype "passive"))
      (node (ref "S6") (pin "1") (pinfunction "S_1") (pintype "passive"))
      (node (ref "S6") (pin "2") (pinfunction "S1_2") (pintype "passive"))
    )
    (net (code "34") (name "/BUTTON7") (class "Default")
      (node (ref "IC3") (pin "5") (pinfunction "G_5") (pintype "input"))
      (node (ref "R4") (pin "1") (pinfunction "1_1") (pintype "passive"))
      (node (ref "S7") (pin "1") (pinfunction "S_1") (pintype "passive"))
      (node (ref "S7") (pin "2") (pinfunction "S1_2") (pintype "passive"))
    )
    (net (code "35") (name "/BUTTON8_GPIO") (class "Default")
      (node (ref "IC3") (pin "6") (pinfunction "H_6") (pintype "input"))
    )
    (net (code "36") (name "/BUTTON_CLK") (class "Default")
      (node (ref "IC3") (pin "2") (pinfunction "CLK_2") (pintype "input"))
      (node (ref "U2") (pin "1") (pinfunction "PD3(INT1)_1") (pintype "bidirectional"))
    )
    (net (code "37") (name "/BUTTON_DAT") (class "Default")
      (node (ref "IC3") (pin "9") (pinfunction "QH_9") (pintype "output"))
      (node (ref "U2") (pin "2") (pinfunction "PD4(XCK/T0)_2") (pintype "bidirectional"))
    )
    (net (code "38") (name "/BUTTON_LOAD") (class "Default")
      (node (ref "IC3") (pin "1") (pinfunction "SH/~{LD}_1") (pintype "input"))
      (node (ref "U2") (pin "32") (pinfunction "PD2(INT0)_32") (pintype "bidirectional"))
    )
    (net (code "39") (name "/C9_GPIO") (class "Default")
      (node (ref "IC1") (pin "54") (pinfunction "PTC9_54") (pintype "bidirectional"))
      (node (ref "X4") (pin "6") (pinfunction "1_6") (pintype "passive"))
    )
    (net (code "40") (name "/C10_GPIO") (class "Default")
      (node (ref "IC1") (pin "55") (pinfunction "PTC10_55") (pintype "bidirectional"))
      (node (ref "X4") (pin "7") (pinfunction "1_7") (pintype "passive"))
    )
    (net (code "41") (name "/C11_GPIO") (class "Default")
      (node (ref "IC1") (pin "56") (pinfunction "PTC11_56") (pintype "bidirectional"))
      (node (ref "X4") (pin "8") (pinfunction "1_8") (pintype "passive"))
    )
    (net (code "42") (name "/D0_GPIO") (class "Default")
      (node (ref "IC1") (pin "57") (pinfunction "PTD0_57") (pintype "bidirectional"))
      (node (ref "X4") (pin "9") (pinfunction "1_9") (pintype "passive"))
    )
    (net (code "43") (name "/D1~{}") (class "Default")
      (node (ref "IC1") (pin "58") (pinfunction "PTD1_58") (pintype "bidirectional"))
    )
    (net (code "44") (name "/D7_GPIO") (class "Default")
      (node (ref "IC1") (pin "64") (pinfunction "PTD7_64") (pintype "bidirectional"))
      (node (ref "X4") (pin "10") (pinfunction "1_10") (pintype "passive"))
    )
    (net (code "45") (name "/DISP_CS") (class "Default")
      (node (ref "IC1") (pin "49") (pinfunction "PTC4_49") (pintype "bidirectional"))
      (node (ref "U$1") (pin "38") (pinfunction "CSX_38") (pintype "input"))
    )
    (net (code "46") (name "/DISP_DC") (class "Default")
      (node (ref "IC1") (pin "46") (pinfunction "PTC3_46") (pintype "bidirectional"))
      (node (ref "U$1") (pin "36") (pinfunction "WRX(D/CX)_36") (pintype "input"))
    )
    (net (code "47") (name "/DISP_RESET") (class "Default")
      (node (ref "IC1") (pin "63") (pinfunction "PTD6_63") (pintype "bidirectional"))
      (node (ref "U$1") (pin "10") (pinfunction "RESET_10") (pintype "input"))
    )
    (net (code "48") (name "/DISP_X+") (class "Default")
      (node (ref "U$1") (pin "44") (pinfunction "X+_44") (pintype "output"))
      (node (ref "U2") (pin "23") (pinfunction "PC0(ADC0)_23") (pintype "bidirectional"))
    )
    (net (code "49") (name "/DISP_X-") (class "Default")
      (node (ref "U$1") (pin "46") (pinfunction "X-_46") (pintype "output"))
      (node (ref "U2") (pin "24") (pinfunction "PC1(ADC1)_24") (pintype "bidirectional"))
    )
    (net (code "50") (name "/DISP_Y+") (class "Default")
      (node (ref "U$1") (pin "45") (pinfunction "Y+_45") (pintype "output"))
      (node (ref "U2") (pin "25") (pinfunction "PC2(ADC2)_25") (pintype "bidirectional"))
    )
    (net (code "51") (name "/DISP_Y-") (class "Default")
      (node (ref "U$1") (pin "47") (pinfunction "Y-_47") (pintype "output"))
      (node (ref "U2") (pin "26") (pinfunction "PC3(ADC3)_26") (pintype "bidirectional"))
    )
    (net (code "52") (name "/ENC1_A") (class "Default")
      (node (ref "SW2") (pin "A") (pinfunction "A_A") (pintype "passive"))
      (node (ref "U2") (pin "14") (pinfunction "PB2(SS/OC1B)_14") (pintype "bidirectional"))
    )
    (net (code "53") (name "/ENC1_B") (class "Default")
      (node (ref "SW2") (pin "B") (pinfunction "B_B") (pintype "passive"))
      (node (ref "U2") (pin "13") (pinfunction "PB1(OC1A)_13") (pintype "bidirectional"))
    )
    (net (code "54") (name "/ENC1_S") (class "Default")
      (node (ref "SW2") (pin "P1") (pinfunction "1_P1") (pintype "passive"))
      (node (ref "U2") (pin "12") (pinfunction "PB0(ICP)_12") (pintype "bidirectional"))
    )
    (net (code "55") (name "/ENC2_A") (class "Default")
      (node (ref "SW1") (pin "A") (pinfunction "A_A") (pintype "passive"))
      (node (ref "U2") (pin "11") (pinfunction "PD7(AIN1)_11") (pintype "bidirectional"))
    )
    (net (code "56") (name "/ENC2_B") (class "Default")
      (node (ref "SW1") (pin "B") (pinfunction "B_B") (pintype "passive"))
      (node (ref "U2") (pin "10") (pinfunction "PD6(AIN0)_10") (pintype "bidirectional"))
    )
    (net (code "57") (name "/ENC2_S") (class "Default")
      (node (ref "SW1") (pin "P1") (pinfunction "1_P1") (pintype "passive"))
      (node (ref "U2") (pin "9") (pinfunction "PD5(T1)_9") (pintype "bidirectional"))
    )
    (net (code "58") (name "/EYE_LED") (class "Default")
      (node (ref "IC1") (pin "61") (pinfunction "PTD4_61") (pintype "bidirectional"))
      (node (ref "R20") (pin "2") (pinfunction "2_2") (pintype "bidirectional"))
    )
    (net (code "59") (name "/GREEN") (class "Default")
      (node (ref "R3") (pin "2") (pinfunction "2_2") (pintype "bidirectional"))
      (node (ref "U4") (pin "13") (pinfunction "PTB1/IRQ_6/UART0_RX/UART0_TX_13") (pintype "bidirectional"))
    )
    (net (code "60") (name "/I2C_SCL") (class "Default")
      (node (ref "IC1") (pin "37") (pinfunction "PTB2_37") (pintype "bidirectional"))
      (node (ref "R1") (pin "1") (pinfunction "1_1") (pintype "bidirectional"))
      (node (ref "U$22") (pin "P$2") (pinfunction "2_P$2") (pintype "bidirectional"))
    )
    (net (code "61") (name "/I2C_SDA") (class "Default")
      (node (ref "IC1") (pin "38") (pinfunction "PTB3_38") (pintype "bidirectional"))
      (node (ref "R18") (pin "1") (pinfunction "1_1") (pintype "bidirectional"))
      (node (ref "U$22") (pin "P$3") (pinfunction "3_P$3") (pintype "bidirectional"))
    )
    (net (code "62") (name "/I2S_BCLK") (class "Default")
      (node (ref "IC1") (pin "41") (pinfunction "PTB18_41") (pintype "bidirectional"))
      (node (ref "U$21") (pin "P$3") (pinfunction "3_P$3") (pintype "bidirectional"))
      (node (ref "U$6") (pin "2") (pinfunction "~{DEM/SCLK}_2") (pintype "bidirectional"))
    )
    (net (code "63") (name "/I2S_DAT") (class "Default")
      (node (ref "IC1") (pin "44") (pinfunction "PTC1_44") (pintype "bidirectional"))
      (node (ref "U$21") (pin "P$4") (pinfunction "4_P$4") (pintype "bidirectional"))
      (node (ref "U$6") (pin "1") (pinfunction "SDIN_1") (pintype "bidirectional"))
    )
    (net (code "64") (name "/I2S_LRC") (class "Default")
      (node (ref "IC1") (pin "45") (pinfunction "PTC2_45") (pintype "bidirectional"))
      (node (ref "U$21") (pin "P$2") (pinfunction "2_P$2") (pintype "bidirectional"))
      (node (ref "U$6") (pin "3") (pinfunction "LRCK_3") (pintype "bidirectional"))
    )
    (net (code "65") (name "/I2S_MCLK") (class "Default")
      (node (ref "IC1") (pin "53") (pinfunction "PTC8_53") (pintype "bidirectional"))
      (node (ref "U$21") (pin "P$1") (pinfunction "1_P$1") (pintype "bidirectional"))
      (node (ref "U$6") (pin "4") (pinfunction "MCLK_4") (pintype "bidirectional"))
    )
    (net (code "66") (name "/INPUTPOWER") (class "Default")
      (node (ref "C16") (pin "+") (pinfunction "1_+") (pintype "bidirectional"))
      (node (ref "C17") (pin "2") (pinfunction "2_2") (pintype "bidirectional"))
      (node (ref "C20") (pin "+") (pinfunction "1_+") (pintype "bidirectional"))
      (node (ref "C29") (pin "2") (pinfunction "2_2") (pintype "bidirectional"))
      (node (ref "C5") (pin "+") (pinfunction "1_+") (pintype "bidirectional"))
      (node (ref "D4") (pin "C") (pinfunction "-_C") (pintype "passive"))
      (node (ref "D5") (pin "C") (pinfunction "-_C") (pintype "passive"))
      (node (ref "IC1") (pin "8") (pinfunction "VREGIN_8") (pintype "bidirectional"))
      (node (ref "IC2") (pin "3") (pinfunction "IN_3") (pintype "input"))
      (node (ref "IC4") (pin "1") (pinfunction "VIN_1") (pintype "bidirectional"))
      (node (ref "IC4") (pin "3") (pinfunction "EN_3") (pintype "bidirectional"))
    )
    (net (code "67") (name "/K20->AVR") (class "Default")
      (node (ref "IC1") (pin "1") (pinfunction "PTE0_1") (pintype "bidirectional"))
      (node (ref "U2") (pin "30") (pinfunction "PD0(RXD)_30") (pintype "bidirectional"))
    )
    (net (code "68") (name "/K20->KL02") (class "Default")
      (node (ref "IC1") (pin "60") (pinfunction "PTD3_60") (pintype "bidirectional"))
      (node (ref "R27") (pin "2") (pinfunction "2_2") (pintype "bidirectional"))
      (node (ref "U4") (pin "18") (pinfunction "PTB4/IRQ_11/I2C0_SDA/UART0_RX_18") (pintype "bidirectional"))
    )
    (net (code "69") (name "/KL02->K20") (class "Default")
      (node (ref "IC1") (pin "59") (pinfunction "PTD2_59") (pintype "bidirectional"))
      (node (ref "R26") (pin "2") (pinfunction "2_2") (pintype "bidirectional"))
      (node (ref "U4") (pin "17") (pinfunction "PTB3/IRQ_10/I2C0_SCL/UART0_TX_17") (pintype "bidirectional"))
    )
    (net (code "70") (name "/LA1") (class "Default")
      (node (ref "U$9") (pin "ANODE") (pinfunction "ANODE_ANODE") (pintype "bidirectional"))
      (node (ref "U4") (pin "2") (pinfunction "PTB7/IRQ_3_2") (pintype "bidirectional"))
    )
    (net (code "71") (name "/LA2") (class "Default")
      (node (ref "U$10") (pin "ANODE") (pinfunction "ANODE_ANODE") (pintype "bidirectional"))
      (node (ref "U4") (pin "9") (pinfunction "PTB10_9") (pintype "bidirectional"))
    )
    (net (code "72") (name "/LA3") (class "Default")
      (node (ref "U$12") (pin "ANODE") (pinfunction "ANODE_ANODE") (pintype "bidirectional"))
      (node (ref "U4") (pin "10") (pinfunction "PTB11_10") (pintype "bidirectional"))
    )
    (net (code "73") (name "/LA4") (class "Default")
      (node (ref "U$13") (pin "ANODE") (pinfunction "ANODE_ANODE") (pintype "bidirectional"))
      (node (ref "U4") (pin "21") (pinfunction "PTB13_21") (pintype "bidirectional"))
    )
    (net (code "74") (name "/LA5") (class "Default")
      (node (ref "U$14") (pin "ANODE") (pinfunction "ANODE_ANODE") (pintype "bidirectional"))
      (node (ref "U4") (pin "7") (pinfunction "PTA5/SPI0_SS_B_7") (pintype "bidirectional"))
    )
    (net (code "75") (name "/LA6") (class "Default")
      (node (ref "U$15") (pin "ANODE") (pinfunction "ANODE_ANODE") (pintype "bidirectional"))
      (node (ref "U4") (pin "8") (pinfunction "PTA6/SPI0_MISO_8") (pintype "bidirectional"))
    )
    (net (code "76") (name "/LA7") (class "Default")
      (node (ref "U$16") (pin "ANODE") (pinfunction "ANODE_ANODE") (pintype "bidirectional"))
      (node (ref "U4") (pin "11") (pinfunction "PTA7/IRQ_4/SPI0_MOSI/SPI0_MISO_11") (pintype "bidirectional"))
    )
    (net (code "77") (name "/LA8") (class "Default")
      (node (ref "U$17") (pin "ANODE") (pinfunction "ANODE_ANODE") (pintype "bidirectional"))
      (node (ref "U4") (pin "15") (pinfunction "PTA8/I2C1_SCL_15") (pintype "bidirectional"))
    )
    (net (code "78") (name "/LA9") (class "Default")
      (node (ref "U$18") (pin "ANODE") (pinfunction "ANODE_ANODE") (pintype "bidirectional"))
      (node (ref "U4") (pin "16") (pinfunction "PTA9/I2C1_SDA_16") (pintype "bidirectional"))
    )
    (net (code "79") (name "/MIDI_IN") (class "Default")
      (node (ref "IC1") (pin "39") (pinfunction "PTB16_39") (pintype "bidirectional"))
      (node (ref "IC5") (pin "5") (pinfunction "COL_5") (pintype "passive"))
      (node (ref "R37") (pin "1") (pinfunction "1_1") (pintype "bidirectional"))
      (node (ref "U1") (pin "9") (pinfunction "4A_9") (pintype "input"))
    )
    (net (code "80") (name "/MIDI_OUT") (class "Default")
      (node (ref "IC1") (pin "40") (pinfunction "PTB17_40") (pintype "bidirectional"))
      (node (ref "U1") (pin "13") (pinfunction "6A_13") (pintype "input"))
    )
    (net (code "81") (name "/MK20_RESET") (class "Default")
      (node (ref "BUTTON1") (pin "1") (pinfunction "A0_1") (pintype "bidirectional"))
      (node (ref "IC1") (pin "34") (pinfunction "RESET_B_34") (pintype "bidirectional"))
      (node (ref "R17") (pin "2") (pinfunction "2_2") (pintype "bidirectional"))
      (node (ref "SWD1") (pin "10") (pinfunction "RESET_10") (pintype "bidirectional"))
    )
    (net (code "82") (name "/N$1") (class "Default")
      (node (ref "R25") (pin "1") (pinfunction "1_1") (pintype "passive"))
      (node (ref "R25") (pin "2") (pinfunction "1_2") (pintype "passive"))
      (node (ref "R25") (pin "3") (pinfunction "1_3") (pintype "passive"))
      (node (ref "R25") (pin "4") (pinfunction "1_4") (pintype "passive"))
      (node (ref "U3") (pin "3") (pinfunction "C_3") (pintype "passive"))
    )
    (net (code "83") (name "/PC4_GPIO") (class "Default")
      (node (ref "U$20") (pin "P$1") (pinfunction "1_P$1") (pintype "bidirectional"))
      (node (ref "U2") (pin "27") (pinfunction "PC4(ADC4/SDA)_27") (pintype "bidirectional"))
    )
    (net (code "84") (name "/PC5_GPIO") (class "Default")
      (node (ref "U$20") (pin "P$2") (pinfunction "2_P$2") (pintype "bidirectional"))
      (node (ref "U2") (pin "28") (pinfunction "PC5(ADC5/SCL)_28") (pintype "bidirectional"))
    )
    (net (code "85") (name "/PTA1") (class "Default")
      (node (ref "SWD2") (pin "10") (pinfunction "RESET_10") (pintype "bidirectional"))
      (node (ref "U4") (pin "23") (pinfunction "PTA1/IRQ_1/LPTMR0_ALT1/RESET_B_23") (pintype "bidirectional"))
    )
    (net (code "86") (name "/PTA3_GPIO") (class "Default")
      (node (ref "U$11") (pin "P$2") (pinfunction "2_P$2") (pintype "bidirectional"))
      (node (ref "U4") (pin "5") (pinfunction "PTA3/EXTAL0/I2C0_SCL/I2C1_SDA_5") (pintype "bidirectional"))
    )
    (net (code "87") (name "/PTA4_GPIO") (class "Default")
      (node (ref "U$11") (pin "P$1") (pinfunction "1_P$1") (pintype "bidirectional"))
      (node (ref "U4") (pin "6") (pinfunction "PTA4/XTAL0/I2C0_SDA/I2C1_SCL_6") (pintype "bidirectional"))
    )
    (net (code "88") (name "/PTA12_GPIO") (class "Default")
      (node (ref "U$11") (pin "P$4") (pinfunction "4_P$4") (pintype "bidirectional"))
      (node (ref "U4") (pin "20") (pinfunction "PTA12/IRQ_13/LPTMR0_ALT2_20") (pintype "bidirectional"))
    )
    (net (code "89") (name "/PTB5_GPIO") (class "Default")
      (node (ref "U$11") (pin "P$5") (pinfunction "5_P$5") (pintype "bidirectional"))
      (node (ref "U4") (pin "19") (pinfunction "PTB5/IRQ_12/NMI_B_19") (pintype "bidirectional"))
    )
    (net (code "90") (name "/PTB6_GPIO") (class "Default")
      (node (ref "U$11") (pin "P$3") (pinfunction "3_P$3") (pintype "bidirectional"))
      (node (ref "U4") (pin "1") (pinfunction "PTB6/IRQ_2/LPTMR0_ALT3_1") (pintype "bidirectional"))
    )
    (net (code "91") (name "/RBLUE") (class "Default")
      (node (ref "R6") (pin "1") (pinfunction "1_1") (pintype "bidirectional"))
      (node (ref "U$10") (pin "B") (pinfunction "B_B") (pintype "bidirectional"))
      (node (ref "U$12") (pin "B") (pinfunction "B_B") (pintype "bidirectional"))
      (node (ref "U$13") (pin "B") (pinfunction "B_B") (pintype "bidirectional"))
      (node (ref "U$14") (pin "B") (pinfunction "B_B") (pintype "bidirectional"))
      (node (ref "U$15") (pin "B") (pinfunction "B_B") (pintype "bidirectional"))
      (node (ref "U$16") (pin "B") (pinfunction "B_B") (pintype "bidirectional"))
      (node (ref "U$17") (pin "B") (pinfunction "B_B") (pintype "bidirectional"))
      (node (ref "U$18") (pin "B") (pinfunction "B_B") (pintype "bidirectional"))
      (node (ref "U$9") (pin "B") (pinfunction "B_B") (pintype "bidirectional"))
    )
    (net (code "92") (name "/RED") (class "Default")
      (node (ref "R2") (pin "2") (pinfunction "2_2") (pintype "bidirectional"))
      (node (ref "U4") (pin "12") (pinfunction "PTB0/IRQ_5/SPI0_SCK_12") (pintype "bidirectional"))
    )
    (net (code "93") (name "/RGREEN") (class "Default")
      (node (ref "R3") (pin "1") (pinfunction "1_1") (pintype "bidirectional"))
      (node (ref "U$10") (pin "G") (pinfunction "G_G") (pintype "bidirectional"))
      (node (ref "U$12") (pin "G") (pinfunction "G_G") (pintype "bidirectional"))
      (node (ref "U$13") (pin "G") (pinfunction "G_G") (pintype "bidirectional"))
      (node (ref "U$14") (pin "G") (pinfunction "G_G") (pintype "bidirectional"))
      (node (ref "U$15") (pin "G") (pinfunction "G_G") (pintype "bidirectional"))
      (node (ref "U$16") (pin "G") (pinfunction "G_G") (pintype "bidirectional"))
      (node (ref "U$17") (pin "G") (pinfunction "G_G") (pintype "bidirectional"))
      (node (ref "U$18") (pin "G") (pinfunction "G_G") (pintype "bidirectional"))
      (node (ref "U$9") (pin "G") (pinfunction "G_G") (pintype "bidirectional"))
    )
    (net (code "94") (name "/RRED") (class "Default")
      (node (ref "R2") (pin "1") (pinfunction "1_1") (pintype "bidirectional"))
      (node (ref "U$10") (pin "R") (pinfunction "R_R") (pintype "bidirectional"))
      (node (ref "U$12") (pin "R") (pinfunction "R_R") (pintype "bidirectional"))
      (node (ref "U$13") (pin "R") (pinfunction "R_R") (pintype "bidirectional"))
      (node (ref "U$14") (pin "R") (pinfunction "R_R") (pintype "bidirectional"))
      (node (ref "U$15") (pin "R") (pinfunction "R_R") (pintype "bidirectional"))
      (node (ref "U$16") (pin "R") (pinfunction "R_R") (pintype "bidirectional"))
      (node (ref "U$17") (pin "R") (pinfunction "R_R") (pintype "bidirectional"))
      (node (ref "U$18") (pin "R") (pinfunction "R_R") (pintype "bidirectional"))
      (node (ref "U$9") (pin "R") (pinfunction "R_R") (pintype "bidirectional"))
    )
    (net (code "95") (name "/SDCARD_CS") (class "Default")
      (node (ref "IC1") (pin "62") (pinfunction "PTD5_62") (pintype "bidirectional"))
      (node (ref "J1") (pin "2") (pinfunction "CS_2") (pintype "bidirectional"))
    )
    (net (code "96") (name "/SERIAL_IN_GPIO") (class "Default")
      (node (ref "IC3") (pin "10") (pinfunction "SER_10") (pintype "input"))
    )
    (net (code "97") (name "/SPI_MISO") (class "Default")
      (node (ref "IC1") (pin "52") (pinfunction "PTC7_52") (pintype "bidirectional"))
      (node (ref "J1") (pin "7") (pinfunction "DO_7") (pintype "bidirectional"))
      (node (ref "U$1") (pin "33") (pinfunction "SDO_33") (pintype "output"))
    )
    (net (code "98") (name "/SPI_MOSI") (class "Default")
      (node (ref "IC1") (pin "51") (pinfunction "PTC6_51") (pintype "bidirectional"))
      (node (ref "J1") (pin "3") (pinfunction "DI_3") (pintype "bidirectional"))
      (node (ref "U$1") (pin "34") (pinfunction "SDI_34") (pintype "input"))
    )
    (net (code "99") (name "/SPI_SCK") (class "Default")
      (node (ref "IC1") (pin "50") (pinfunction "PTC5_50") (pintype "bidirectional"))
      (node (ref "J1") (pin "5") (pinfunction "SCLK_5") (pintype "bidirectional"))
      (node (ref "U$1") (pin "37") (pinfunction "D/CX(SCL)_37") (pintype "input"))
    )
    (net (code "100") (name "/USBMINUS") (class "Default")
      (node (ref "IC1") (pin "6") (pinfunction "USB0_DM_6") (pintype "bidirectional"))
      (node (ref "R31") (pin "2") (pinfunction "2_2") (pintype "bidirectional"))
    )
    (net (code "101") (name "/USBPLUS") (class "Default")
      (node (ref "IC1") (pin "5") (pinfunction "USB0_DP_5") (pintype "bidirectional"))
      (node (ref "R32") (pin "2") (pinfunction "2_2") (pintype "bidirectional"))
    )
    (net (code "102") (name "/USB_N") (class "Default")
      (node (ref "J2") (pin "3") (pinfunction "DP_3") (pintype "bidirectional"))
      (node (ref "R32") (pin "1") (pinfunction "1_1") (pintype "bidirectional"))
      (node (ref "X1") (pin "2") (pinfunction "D-_2") (pintype "bidirectional"))
    )
    (net (code "103") (name "/USB_P") (class "Default")
      (node (ref "J2") (pin "2") (pinfunction "DM_2") (pintype "bidirectional"))
      (node (ref "R31") (pin "1") (pinfunction "1_1") (pintype "bidirectional"))
      (node (ref "X1") (pin "3") (pinfunction "D+_3") (pintype "bidirectional"))
    )
    (net (code "104") (name "/VUSB") (class "Default")
      (node (ref "J2") (pin "1") (pinfunction "VCC_1") (pintype "bidirectional"))
      (node (ref "L4") (pin "1") (pinfunction "1_1") (pintype "passive"))
      (node (ref "X1") (pin "1") (pinfunction "VBUS_1") (pintype "power_in"))
    )
    (net (code "105") (name "3.3V") (class "Default")
      (node (ref "AVR_ISP") (pin "2") (pinfunction "2_2") (pintype "bidirectional"))
      (node (ref "C1") (pin "2") (pinfunction "2_2") (pintype "bidirectional"))
      (node (ref "C15") (pin "+") (pinfunction "1_+") (pintype "bidirectional"))
      (node (ref "C18") (pin "2") (pinfunction "2_2") (pintype "bidirectional"))
      (node (ref "C2") (pin "2") (pinfunction "2_2") (pintype "bidirectional"))
      (node (ref "C25") (pin "2") (pinfunction "2_2") (pintype "bidirectional"))
      (node (ref "C3") (pin "2") (pinfunction "2_2") (pintype "bidirectional"))
      (node (ref "C33") (pin "2") (pinfunction "2_2") (pintype "bidirectional"))
      (node (ref "C34") (pin "2") (pinfunction "2_2") (pintype "bidirectional"))
      (node (ref "C35") (pin "2") (pinfunction "2_2") (pintype "bidirectional"))
      (node (ref "C36") (pin "2") (pinfunction "2_2") (pintype "bidirectional"))
      (node (ref "C37") (pin "2") (pinfunction "2_2") (pintype "bidirectional"))
      (node (ref "C4") (pin "2") (pinfunction "2_2") (pintype "bidirectional"))
      (node (ref "C40") (pin "2") (pinfunction "2_2") (pintype "bidirectional"))
      (node (ref "C41") (pin "2") (pinfunction "2_2") (pintype "bidirectional"))
      (node (ref "C42") (pin "2") (pinfunction "2_2") (pintype "bidirectional"))
      (node (ref "C6") (pin "2") (pinfunction "2_2") (pintype "bidirectional"))
      (node (ref "C8") (pin "2") (pinfunction "2_2") (pintype "bidirectional"))
      (node (ref "C9") (pin "2") (pinfunction "2_2") (pintype "bidirectional"))
      (node (ref "IC1") (pin "21") (pinfunction "VBAT_21") (pintype "bidirectional"))
      (node (ref "IC1") (pin "3") (pinfunction "VDD_3") (pintype "bidirectional"))
      (node (ref "IC1") (pin "30") (pinfunction "VDD_30") (pintype "bidirectional"))
      (node (ref "IC1") (pin "48") (pinfunction "VDD_48") (pintype "bidirectional"))
      (node (ref "IC2") (pin "2") (pinfunction "OUT_2") (pintype "passive"))
      (node (ref "IC2") (pin "4") (pinfunction "OUT_4") (pintype "passive"))
      (node (ref "IC3") (pin "16") (pinfunction "VCC_16") (pintype "power_in"))
      (node (ref "J1") (pin "4") (pinfunction "VDD_4") (pintype "bidirectional"))
      (node (ref "JP6") (pin "1") (pinfunction "1_1") (pintype "passive"))
      (node (ref "L2") (pin "2") (pinfunction "2_2") (pintype "passive"))
      (node (ref "R1") (pin "2") (pinfunction "2_2") (pintype "bidirectional"))
      (node (ref "R11") (pin "1") (pinfunction "1_1") (pintype "bidirectional"))
      (node (ref "R14") (pin "2") (pinfunction "2_2") (pintype "bidirectional"))
      (node (ref "R17") (pin "1") (pinfunction "1_1") (pintype "bidirectional"))
      (node (ref "R18") (pin "2") (pinfunction "2_2") (pintype "bidirectional"))
      (node (ref "R22") (pin "1") (pinfunction "1_1") (pintype "bidirectional"))
      (node (ref "R23") (pin "5") (pinfunction "2_5") (pintype "passive"))
      (node (ref "R23") (pin "6") (pinfunction "2_6") (pintype "passive"))
      (node (ref "R23") (pin "7") (pinfunction "2_7") (pintype "passive"))
      (node (ref "R23") (pin "8") (pinfunction "2_8") (pintype "passive"))
      (node (ref "R24") (pin "2") (pinfunction "2_2") (pintype "bidirectional"))
      (node (ref "R26") (pin "1") (pinfunction "1_1") (pintype "bidirectional"))
      (node (ref "R27") (pin "1") (pinfunction "1_1") (pintype "bidirectional"))
      (node (ref "R37") (pin "2") (pinfunction "2_2") (pintype "bidirectional"))
      (node (ref "R4") (pin "6") (pinfunction "2_6") (pintype "passive"))
      (node (ref "R4") (pin "7") (pinfunction "2_7") (pintype "passive"))
      (node (ref "R4") (pin "8") (pinfunction "2_8") (pintype "passive"))
      (node (ref "R5") (pin "2") (pinfunction "2_2") (pintype "bidirectional"))
      (node (ref "R7") (pin "2") (pinfunction "2_2") (pintype "bidirectional"))
      (node (ref "R8") (pin "2") (pinfunction "2_2") (pintype "bidirectional"))
      (node (ref "R9") (pin "2") (pinfunction "2_2") (pintype "bidirectional"))
      (node (ref "SWD1") (pin "1") (pinfunction "VCC_1") (pintype "bidirectional"))
      (node (ref "SWD2") (pin "1") (pinfunction "VCC_1") (pintype "bidirectional"))
      (node (ref "U$1") (pin "35") (pinfunction "RD_35") (pintype "input"))
      (node (ref "U$1") (pin "40") (pinfunction "VDDI_40") (pintype "power_in"))
      (node (ref "U$1") (pin "41") (pinfunction "VDDI2_41") (pintype "power_in"))
      (node (ref "U$1") (pin "42") (pinfunction "VCI_42") (pintype "power_in"))
      (node (ref "U$1") (pin "7") (pinfunction "IM1_7") (pintype "input"))
      (node (ref "U$1") (pin "8") (pinfunction "IM2_8") (pintype "input"))
      (node (ref "U$1") (pin "9") (pinfunction "IM3_9") (pintype "input"))
      (node (ref "U$22") (pin "P$1") (pinfunction "1_P$1") (pintype "bidirectional"))
      (node (ref "U1") (pin "14") (pinfunction "VCC_14") (pintype "power_in"))
      (node (ref "U2") (pin "18") (pinfunction "AVCC_18") (pintype "bidirectional"))
      (node (ref "U2") (pin "20") (pinfunction "AREF_20") (pintype "bidirectional"))
      (node (ref "U2") (pin "4") (pinfunction "VCC_4") (pintype "bidirectional"))
      (node (ref "U2") (pin "6") (pinfunction "VCC_6") (pintype "bidirectional"))
      (node (ref "U3") (pin "2") (pinfunction "E_2") (pintype "passive"))
      (node (ref "U4") (pin "3") (pinfunction "VDD_VREFH_3") (pintype "power_in"))
    )
    (net (code "106") (name "DGND") (class "Default")
      (node (ref "AVR_ISP") (pin "6") (pinfunction "6_6") (pintype "bidirectional"))
      (node (ref "BUTTON1") (pin "2") (pinfunction "B0_2") (pintype "bidirectional"))
      (node (ref "C1") (pin "1") (pinfunction "1_1") (pintype "bidirectional"))
      (node (ref "C15") (pin "-") (pinfunction "2_-") (pintype "bidirectional"))
      (node (ref "C16") (pin "-") (pinfunction "2_-") (pintype "bidirectional"))
      (node (ref "C17") (pin "1") (pinfunction "1_1") (pintype "bidirectional"))
      (node (ref "C18") (pin "1") (pinfunction "1_1") (pintype "bidirectional"))
      (node (ref "C2") (pin "1") (pinfunction "1_1") (pintype "bidirectional"))
      (node (ref "C23") (pin "1") (pinfunction "1_1") (pintype "bidirectional"))
      (node (ref "C24") (pin "1") (pinfunction "1_1") (pintype "bidirectional"))
      (node (ref "C25") (pin "1") (pinfunction "1_1") (pintype "bidirectional"))
      (node (ref "C3") (pin "1") (pinfunction "1_1") (pintype "bidirectional"))
      (node (ref "C33") (pin "1") (pinfunction "1_1") (pintype "bidirectional"))
      (node (ref "C34") (pin "1") (pinfunction "1_1") (pintype "bidirectional"))
      (node (ref "C35") (pin "1") (pinfunction "1_1") (pintype "bidirectional"))
      (node (ref "C36") (pin "1") (pinfunction "1_1") (pintype "bidirectional"))
      (node (ref "C37") (pin "1") (pinfunction "1_1") (pintype "bidirectional"))
      (node (ref "C38") (pin "1") (pinfunction "1_1") (pintype "bidirectional"))
      (node (ref "C39") (pin "1") (pinfunction "1_1") (pintype "bidirectional"))
      (node (ref "C4") (pin "1") (pinfunction "1_1") (pintype "bidirectional"))
      (node (ref "C40") (pin "1") (pinfunction "1_1") (pintype "bidirectional"))
      (node (ref "C41") (pin "1") (pinfunction "1_1") (pintype "bidirectional"))
      (node (ref "C42") (pin "1") (pinfunction "1_1") (pintype "bidirectional"))
      (node (ref "C5") (pin "-") (pinfunction "2_-") (pintype "bidirectional"))
      (node (ref "C6") (pin "1") (pinfunction "1_1") (pintype "bidirectional"))
      (node (ref "C8") (pin "1") (pinfunction "1_1") (pintype "bidirectional"))
      (node (ref "C9") (pin "1") (pinfunction "1_1") (pintype "bidirectional"))
      (node (ref "IC1") (pin "15") (pinfunction "VREFL_15") (pintype "bidirectional"))
      (node (ref "IC1") (pin "16") (pinfunction "VSSA_16") (pintype "bidirectional"))
      (node (ref "IC1") (pin "31") (pinfunction "VSS_31") (pintype "bidirectional"))
      (node (ref "IC1") (pin "4") (pinfunction "VSS_4") (pintype "bidirectional"))
      (node (ref "IC1") (pin "47") (pinfunction "VSS_47") (pintype "bidirectional"))
      (node (ref "IC2") (pin "1") (pinfunction "ADJ_1") (pintype "input"))
      (node (ref "IC3") (pin "15") (pinfunction "INH_15") (pintype "input"))
      (node (ref "IC3") (pin "8") (pinfunction "GND_8") (pintype "power_in"))
      (node (ref "IC5") (pin "4") (pinfunction "EMI_4") (pintype "passive"))
      (node (ref "IC6") (pin "1") (pinfunction "ADJ_1") (pintype "input"))
      (node (ref "J1") (pin "6") (pinfunction "VSS_6") (pintype "bidirectional"))
      (node (ref "J1") (pin "G1") (pinfunction "G1_G1") (pintype "bidirectional"))
      (node (ref "J1") (pin "G2") (pinfunction "G2_G2") (pintype "bidirectional"))
      (node (ref "J1") (pin "G3") (pinfunction "G3_G3") (pintype "bidirectional"))
      (node (ref "J1") (pin "G4") (pinfunction "G4_G4") (pintype "bidirectional"))
      (node (ref "J2") (pin "5") (pinfunction "GND_5") (pintype "bidirectional"))
      (node (ref "JP6") (pin "2") (pinfunction "2_2") (pintype "passive"))
      (node (ref "L1") (pin "1") (pinfunction "1_1") (pintype "passive"))
      (node (ref "L3") (pin "2") (pinfunction "2_2") (pintype "passive"))
      (node (ref "L5") (pin "2") (pinfunction "2_2") (pintype "passive"))
      (node (ref "L6") (pin "2") (pinfunction "2_2") (pintype "passive"))
      (node (ref "L7") (pin "2") (pinfunction "2_2") (pintype "passive"))
      (node (ref "LED_EYE") (pin "C") (pinfunction "C_C") (pintype "passive"))
      (node (ref "LED_PWR") (pin "C") (pinfunction "C_C") (pintype "passive"))
      (node (ref "PORT_MIDI-OUT") (pin "2") (pinfunction "2_2") (pintype "passive"))
      (node (ref "PORT_MIDI-OUT") (pin "PE") (pinfunction "MT_PE") (pintype "passive"))
      (node (ref "PORT_MIDI-OUT") (pin "PE1") (pinfunction "MT_PE1") (pintype "passive"))
      (node (ref "PORT_MIDI-OUT") (pin "PE2") (pinfunction "MT_PE2") (pintype "passive"))
      (node (ref "PORT_MIDI-OUT") (pin "PE@") (pinfunction "MT_PE@") (pintype "passive"))
      (node (ref "PORT_MIDI-THROUGH") (pin "2") (pinfunction "2_2") (pintype "passive"))
      (node (ref "PORT_MIDI-THROUGH") (pin "PE") (pinfunction "MT_PE") (pintype "passive"))
      (node (ref "PORT_MIDI-THROUGH") (pin "PE1") (pinfunction "MT_PE1") (pintype "passive"))
      (node (ref "PORT_MIDI-THROUGH") (pin "PE2") (pinfunction "MT_PE2") (pintype "passive"))
      (node (ref "PORT_MIDI-THROUGH") (pin "PE@") (pinfunction "MT_PE@") (pintype "passive"))
      (node (ref "S1") (pin "3") (pinfunction "P_3") (pintype "passive"))
      (node (ref "S1") (pin "4") (pinfunction "P1_4") (pintype "passive"))
      (node (ref "S2") (pin "3") (pinfunction "P_3") (pintype "passive"))
      (node (ref "S2") (pin "4") (pinfunction "P1_4") (pintype "passive"))
      (node (ref "S3") (pin "3") (pinfunction "P_3") (pintype "passive"))
      (node (ref "S3") (pin "4") (pinfunction "P1_4") (pintype "passive"))
      (node (ref "S4") (pin "3") (pinfunction "P_3") (pintype "passive"))
      (node (ref "S4") (pin "4") (pinfunction "P1_4") (pintype "passive"))
      (node (ref "S5") (pin "3") (pinfunction "P_3") (pintype "passive"))
      (node (ref "S5") (pin "4") (pinfunction "P1_4") (pintype "passive"))
      (node (ref "S6") (pin "3") (pinfunction "P_3") (pintype "passive"))
      (node (ref "S6") (pin "4") (pinfunction "P1_4") (pintype "passive"))
      (node (ref "S7") (pin "3") (pinfunction "P_3") (pintype "passive"))
      (node (ref "S7") (pin "4") (pinfunction "P1_4") (pintype "passive"))
      (node (ref "SW1") (pin "C") (pinfunction "C_C") (pintype "passive"))
      (node (ref "SW1") (pin "P2") (pinfunction "2_P2") (pintype "passive"))
      (node (ref "SW2") (pin "P2") (pinfunction "2_P2") (pintype "passive"))
      (node (ref "SWD1") (pin "3") (pinfunction "GND1_3") (pintype "bidirectional"))
      (node (ref "SWD1") (pin "5") (pinfunction "GND2_5") (pintype "bidirectional"))
      (node (ref "SWD2") (pin "3") (pinfunction "GND1_3") (pintype "bidirectional"))
      (node (ref "SWD2") (pin "5") (pinfunction "GND2_5") (pintype "bidirectional"))
      (node (ref "U$1") (pin "1") (pinfunction "LEDK_1") (pintype "power_in"))
      (node (ref "U$1") (pin "11") (pinfunction "VSYNC_11") (pintype "input"))
      (node (ref "U$1") (pin "12") (pinfunction "HSYNC_12") (pintype "input"))
      (node (ref "U$1") (pin "13") (pinfunction "DOTCLK_13") (pintype "input"))
      (node (ref "U$1") (pin "14") (pinfunction "DE_14") (pintype "bidirectional"))
      (node (ref "U$1") (pin "15") (pinfunction "DB17_15") (pintype "bidirectional"))
      (node (ref "U$1") (pin "16") (pinfunction "DB16_16") (pintype "bidirectional"))
      (node (ref "U$1") (pin "17") (pinfunction "DB15_17") (pintype "bidirectional"))
      (node (ref "U$1") (pin "18") (pinfunction "DB14_18") (pintype "bidirectional"))
      (node (ref "U$1") (pin "19") (pinfunction "DB13_19") (pintype "bidirectional"))
      (node (ref "U$1") (pin "20") (pinfunction "DB12_20") (pintype "bidirectional"))
      (node (ref "U$1") (pin "21") (pinfunction "DB11_21") (pintype "bidirectional"))
      (node (ref "U$1") (pin "22") (pinfunction "DB10_22") (pintype "bidirectional"))
      (node (ref "U$1") (pin "23") (pinfunction "DB9_23") (pintype "bidirectional"))
      (node (ref "U$1") (pin "24") (pinfunction "DB8_24") (pintype "bidirectional"))
      (node (ref "U$1") (pin "25") (pinfunction "DB7_25") (pintype "bidirectional"))
      (node (ref "U$1") (pin "26") (pinfunction "DB6_26") (pintype "bidirectional"))
      (node (ref "U$1") (pin "27") (pinfunction "DB5_27") (pintype "bidirectional"))
      (node (ref "U$1") (pin "28") (pinfunction "DB4_28") (pintype "bidirectional"))
      (node (ref "U$1") (pin "29") (pinfunction "DB3_29") (pintype "bidirectional"))
      (node (ref "U$1") (pin "30") (pinfunction "DB2_30") (pintype "bidirectional"))
      (node (ref "U$1") (pin "31") (pinfunction "DB1_31") (pintype "bidirectional"))
      (node (ref "U$1") (pin "32") (pinfunction "DB0_32") (pintype "bidirectional"))
      (node (ref "U$1") (pin "43") (pinfunction "GND_43") (pintype "power_in"))
      (node (ref "U$1") (pin "48") (pinfunction "GND2_48") (pintype "power_in"))
      (node (ref "U$1") (pin "49") (pinfunction "GND3_49") (pintype "power_in"))
      (node (ref "U$1") (pin "50") (pinfunction "GND4_50") (pintype "power_in"))
      (node (ref "U$1") (pin "6") (pinfunction "IM0_6") (pintype "input"))
      (node (ref "U$22") (pin "P$4") (pinfunction "4_P$4") (pintype "bidirectional"))
      (node (ref "U$7") (pin "RING") (pinfunction "RING_RING") (pintype "bidirectional"))
      (node (ref "U$7") (pin "RING_SW") (pinfunction "RING_SW_RING_SW") (pintype "bidirectional"))
      (node (ref "U1") (pin "1") (pinfunction "1A_1") (pintype "input"))
      (node (ref "U1") (pin "3") (pinfunction "2A_3") (pintype "input"))
      (node (ref "U1") (pin "7") (pinfunction "GND_7") (pintype "passive"))
      (node (ref "U2") (pin "21") (pinfunction "GND_21") (pintype "bidirectional"))
      (node (ref "U2") (pin "3") (pinfunction "GND_3") (pintype "bidirectional"))
      (node (ref "U2") (pin "5") (pinfunction "GND_5") (pintype "bidirectional"))
      (node (ref "U4") (pin "25") (pinfunction "E_PAD_25") (pintype "passive"))
      (node (ref "U4") (pin "4") (pinfunction "VREFL_VSS_4") (pintype "passive"))
      (node (ref "X1") (pin "4") (pinfunction "GND_4") (pintype "power_in"))
    )
    (net (code "107") (name "Net-(C11-1)") (class "Default")
      (node (ref "C11") (pin "+") (pinfunction "1_+") (pintype "bidirectional"))
      (node (ref "D3") (pin "3") (pinfunction "C1A2_3") (pintype "passive"))
      (node (ref "U$6") (pin "10") (pinfunction "AOUTR_10") (pintype "bidirectional"))
    )
    (net (code "108") (name "Net-(C11-2)") (class "Default")
      (node (ref "C11") (pin "-") (pinfunction "2_-") (pintype "bidirectional"))
      (node (ref "R13") (pin "1") (pinfunction "1_1") (pintype "passive"))
      (node (ref "R15") (pin "2") (pinfunction "2_2") (pintype "passive"))
    )
    (net (code "109") (name "Net-(C12-1)") (class "Default")
      (node (ref "C12") (pin "+") (pinfunction "1_+") (pintype "bidirectional"))
      (node (ref "D2") (pin "3") (pinfunction "C1A2_3") (pintype "passive"))
      (node (ref "U$6") (pin "7") (pinfunction "AOUTL_7") (pintype "bidirectional"))
    )
    (net (code "110") (name "Net-(C12-2)") (class "Default")
      (node (ref "C12") (pin "-") (pinfunction "2_-") (pintype "bidirectional"))
      (node (ref "R12") (pin "1") (pinfunction "1_1") (pintype "passive"))
      (node (ref "R16") (pin "2") (pinfunction "2_2") (pintype "passive"))
    )
    (net (code "111") (name "Net-(C13-1)") (class "Default")
      (node (ref "C13") (pin "+") (pinfunction "1_+") (pintype "bidirectional"))
      (node (ref "C49") (pin "1") (pinfunction "1_1") (pintype "passive"))
      (node (ref "U$6") (pin "5") (pinfunction "VQ_5") (pintype "bidirectional"))
    )
    (net (code "112") (name "Net-(C44-Pad2)") (class "Default")
      (node (ref "C44") (pin "2") (pinfunction "2_2") (pintype "passive"))
      (node (ref "FB2") (pin "1") (pinfunction "1_1") (pintype "passive"))
      (node (ref "R13") (pin "2") (pinfunction "2_2") (pintype "passive"))
    )
    (net (code "113") (name "Net-(C45-Pad2)") (class "Default")
      (node (ref "C45") (pin "2") (pinfunction "2_2") (pintype "passive"))
      (node (ref "FB1") (pin "1") (pinfunction "1_1") (pintype "passive"))
      (node (ref "R12") (pin "2") (pinfunction "2_2") (pintype "passive"))
    )
    (net (code "114") (name "Net-(D1-+)") (class "Default")
      (node (ref "D1") (pin "A") (pinfunction "+_A") (pintype "passive"))
      (node (ref "IC5") (pin "2") (pinfunction "C_2") (pintype "passive"))
      (node (ref "PORT_MIDI-IN") (pin "5") (pinfunction "5_5") (pintype "passive"))
    )
    (net (code "115") (name "Net-(D1--)") (class "Default")
      (node (ref "D1") (pin "C") (pinfunction "-_C") (pintype "passive"))
      (node (ref "IC5") (pin "1") (pinfunction "A_1") (pintype "passive"))
      (node (ref "R38") (pin "1") (pinfunction "1_1") (pintype "bidirectional"))
    )
    (net (code "116") (name "Net-(D4-+)") (class "Default")
      (node (ref "D4") (pin "A") (pinfunction "+_A") (pintype "passive"))
      (node (ref "IC6") (pin "2") (pinfunction "OUT_2") (pintype "passive"))
      (node (ref "IC6") (pin "4") (pinfunction "OUT_4") (pintype "passive"))
    )
    (net (code "117") (name "Net-(IC1-PTA18)") (class "Default")
      (node (ref "C23") (pin "2") (pinfunction "2_2") (pintype "bidirectional"))
      (node (ref "IC1") (pin "32") (pinfunction "PTA18_32") (pintype "bidirectional"))
      (node (ref "X2") (pin "2") (pinfunction "2_2") (pintype "passive"))
    )
    (net (code "118") (name "Net-(IC1-PTA19)") (class "Default")
      (node (ref "C24") (pin "2") (pinfunction "2_2") (pintype "bidirectional"))
      (node (ref "IC1") (pin "33") (pinfunction "PTA19_33") (pintype "bidirectional"))
      (node (ref "X2") (pin "1") (pinfunction "1_1") (pintype "passive"))
    )
    (net (code "119") (name "Net-(IC1-VDDA)") (class "Default")
      (node (ref "IC1") (pin "13") (pinfunction "VDDA_13") (pintype "bidirectional"))
      (node (ref "IC1") (pin "14") (pinfunction "VREFH_14") (pintype "bidirectional"))
      (node (ref "L2") (pin "1") (pinfunction "1_1") (pintype "passive"))
    )
    (net (code "120") (name "Net-(IC4-BYP)") (class "Default")
      (node (ref "C32") (pin "2") (pinfunction "2_2") (pintype "bidirectional"))
      (node (ref "IC4") (pin "4") (pinfunction "BYP_4") (pintype "bidirectional"))
    )
    (net (code "121") (name "Net-(IC5-BAS)") (class "Default")
      (node (ref "IC5") (pin "6") (pinfunction "BAS_6") (pintype "passive"))
      (node (ref "TP2") (pin "P$1") (pinfunction "1_P$1") (pintype "bidirectional"))
    )
    (net (code "122") (name "Net-(IC6-IN)") (class "Default")
      (node (ref "IC6") (pin "3") (pinfunction "IN_3") (pintype "input"))
      (node (ref "U$7") (pin "TIP") (pinfunction "TIP_TIP") (pintype "bidirectional"))
    )
    (net (code "123") (name "Net-(J1-CDN)") (class "Default")
      (node (ref "J1") (pin "9") (pinfunction "CDN_9") (pintype "bidirectional"))
      (node (ref "R24") (pin "1") (pinfunction "1_1") (pintype "bidirectional"))
    )
    (net (code "124") (name "Net-(J1-DATA1)") (class "Default")
      (node (ref "J1") (pin "8") (pinfunction "DATA1_8") (pintype "bidirectional"))
      (node (ref "R7") (pin "1") (pinfunction "1_1") (pintype "bidirectional"))
    )
    (net (code "125") (name "Net-(J1-DATA2)") (class "Default")
      (node (ref "J1") (pin "1") (pinfunction "DATA2_1") (pintype "bidirectional"))
      (node (ref "R5") (pin "1") (pinfunction "1_1") (pintype "bidirectional"))
    )
    (net (code "126") (name "Net-(LED_EYE-PadA)") (class "Default")
      (node (ref "LED_EYE") (pin "A") (pinfunction "A_A") (pintype "passive"))
      (node (ref "R20") (pin "1") (pinfunction "1_1") (pintype "bidirectional"))
    )
    (net (code "127") (name "Net-(LED_PWR-PadA)") (class "Default")
      (node (ref "LED_PWR") (pin "A") (pinfunction "A_A") (pintype "passive"))
      (node (ref "R14") (pin "1") (pinfunction "1_1") (pintype "bidirectional"))
    )
    (net (code "128") (name "Net-(PORT_MIDI-IN-Pad4)") (class "Default")
      (node (ref "PORT_MIDI-IN") (pin "4") (pinfunction "4_4") (pintype "passive"))
      (node (ref "R38") (pin "2") (pinfunction "2_2") (pintype "bidirectional"))
    )
    (net (code "129") (name "Net-(PORT_MIDI-OUT-Pad4)") (class "Default")
      (node (ref "PORT_MIDI-OUT") (pin "4") (pinfunction "4_4") (pintype "passive"))
      (node (ref "R11") (pin "2") (pinfunction "2_2") (pintype "bidirectional"))
    )
    (net (code "130") (name "Net-(PORT_MIDI-OUT-Pad5)") (class "Default")
      (node (ref "PORT_MIDI-OUT") (pin "5") (pinfunction "5_5") (pintype "passive"))
      (node (ref "R10") (pin "1") (pinfunction "1_1") (pintype "bidirectional"))
    )
    (net (code "131") (name "Net-(PORT_MIDI-THROUGH-Pad4)") (class "Default")
      (node (ref "PORT_MIDI-THROUGH") (pin "4") (pinfunction "4_4") (pintype "passive"))
      (node (ref "R22") (pin "2") (pinfunction "2_2") (pintype "bidirectional"))
    )
    (net (code "132") (name "Net-(PORT_MIDI-THROUGH-Pad5)") (class "Default")
      (node (ref "PORT_MIDI-THROUGH") (pin "5") (pinfunction "5_5") (pintype "passive"))
      (node (ref "R21") (pin "1") (pinfunction "1_1") (pintype "bidirectional"))
    )
    (net (code "133") (name "Net-(R25A-2)") (class "Default")
      (node (ref "R25") (pin "8") (pinfunction "2_8") (pintype "passive"))
      (node (ref "U$1") (pin "5") (pinfunction "LEDA4_5") (pintype "power_in"))
    )
    (net (code "134") (name "Net-(R25B-2)") (class "Default")
      (node (ref "R25") (pin "7") (pinfunction "2_7") (pintype "passive"))
      (node (ref "U$1") (pin "4") (pinfunction "LEDA3_4") (pintype "power_in"))
    )
    (net (code "135") (name "Net-(R25C-2)") (class "Default")
      (node (ref "R25") (pin "6") (pinfunction "2_6") (pintype "passive"))
      (node (ref "U$1") (pin "3") (pinfunction "LEDA2_3") (pintype "power_in"))
    )
    (net (code "136") (name "Net-(R25D-2)") (class "Default")
      (node (ref "R25") (pin "5") (pinfunction "2_5") (pintype "passive"))
      (node (ref "U$1") (pin "2") (pinfunction "LEDA1_2") (pintype "power_in"))
    )
    (net (code "137") (name "Net-(SWD2-SWCLK)") (class "Default")
      (node (ref "SWD2") (pin "4") (pinfunction "SWCLK_4") (pintype "bidirectional"))
      (node (ref "U4") (pin "22") (pinfunction "PTA0/IRQ_0/SWD_CLK_22") (pintype "bidirectional"))
    )
    (net (code "138") (name "Net-(SWD2-SWDIO)") (class "Default")
      (node (ref "SWD2") (pin "2") (pinfunction "SWDIO_2") (pintype "bidirectional"))
      (node (ref "U4") (pin "24") (pinfunction "PTA2/SWD_DIO_24") (pintype "bidirectional"))
    )
    (net (code "139") (name "Net-(U$6-FILT+)") (class "Default")
      (node (ref "C50") (pin "1") (pinfunction "1_1") (pintype "passive"))
      (node (ref "U$6") (pin "6") (pinfunction "FILT+_6") (pintype "bidirectional"))
    )
    (net (code "140") (name "Net-(U1-3A)") (class "Default")
      (node (ref "U1") (pin "5") (pinfunction "3A_5") (pintype "input"))
      (node (ref "U1") (pin "8") (pinfunction "~{4Y}_8") (pintype "output"))
    )
    (net (code "141") (name "Net-(U1-5A)") (class "Default")
      (node (ref "U1") (pin "11") (pinfunction "5A_11") (pintype "input"))
      (node (ref "U1") (pin "12") (pinfunction "~{6Y}_12") (pintype "output"))
    )
    (net (code "142") (name "Net-(U1-~{3Y})") (class "Default")
      (node (ref "R21") (pin "2") (pinfunction "2_2") (pintype "bidirectional"))
      (node (ref "U1") (pin "6") (pinfunction "~{3Y}_6") (pintype "output"))
    )
    (net (code "143") (name "Net-(U1-~{5Y})") (class "Default")
      (node (ref "R10") (pin "2") (pinfunction "2_2") (pintype "bidirectional"))
      (node (ref "U1") (pin "10") (pinfunction "~{5Y}_10") (pintype "output"))
    )
    (net (code "144") (name "Net-(U2-PB6(XTAL1{slash}TOSC1))") (class "Default")
      (node (ref "C38") (pin "2") (pinfunction "2_2") (pintype "bidirectional"))
      (node (ref "U2") (pin "7") (pinfunction "PB6(XTAL1/TOSC1)_7") (pintype "bidirectional"))
      (node (ref "X3") (pin "2") (pinfunction "2_2") (pintype "passive"))
    )
    (net (code "145") (name "Net-(U2-PB7(XTAL2{slash}TOSC2))") (class "Default")
      (node (ref "C39") (pin "2") (pinfunction "2_2") (pintype "bidirectional"))
      (node (ref "U2") (pin "8") (pinfunction "PB7(XTAL2/TOSC2)_8") (pintype "bidirectional"))
      (node (ref "X3") (pin "1") (pinfunction "1_1") (pintype "passive"))
    )
    (net (code "146") (name "Net-(U3-B)") (class "Default")
      (node (ref "R19") (pin "1") (pinfunction "1_1") (pintype "bidirectional"))
      (node (ref "U3") (pin "1") (pinfunction "B_1") (pintype "passive"))
    )
    (net (code "147") (name "Net-(X1-GND1)") (class "Default")
      (node (ref "J2") (pin "E1") (pinfunction "GND_E1") (pintype "bidirectional"))
      (node (ref "J2") (pin "E2") (pinfunction "GND_E2") (pintype "bidirectional"))
      (node (ref "J2") (pin "P1") (pinfunction "GND_P1") (pintype "bidirectional"))
      (node (ref "J2") (pin "P2") (pinfunction "GND_P2") (pintype "bidirectional"))
      (node (ref "L1") (pin "2") (pinfunction "2_2") (pintype "passive"))
      (node (ref "X1") (pin "P$1") (pinfunction "GND1_P$1") (pintype "power_in"))
      (node (ref "X1") (pin "P$2") (pinfunction "GND2_P$2") (pintype "power_in"))
    )
    (net (code "148") (name "unconnected-(BUTTON1-A1-Pad4)") (class "Default")
      (node (ref "BUTTON1") (pin "4") (pinfunction "A1_4") (pintype "bidirectional"))
    )
    (net (code "149") (name "unconnected-(BUTTON1-B1-Pad3)") (class "Default")
      (node (ref "BUTTON1") (pin "3") (pinfunction "B1_3") (pintype "bidirectional"))
    )
    (net (code "150") (name "unconnected-(IC1-ADC0_DM0-Pad10)") (class "Default")
      (node (ref "IC1") (pin "10") (pinfunction "ADC0_DM0_10") (pintype "bidirectional"))
    )
    (net (code "151") (name "unconnected-(IC1-ADC0_DM3-Pad12)") (class "Default")
      (node (ref "IC1") (pin "12") (pinfunction "ADC0_DM3_12") (pintype "bidirectional"))
    )
    (net (code "152") (name "unconnected-(IC1-ADC0_DP0-Pad9)") (class "Default")
      (node (ref "IC1") (pin "9") (pinfunction "ADC0_DP0_9") (pintype "bidirectional"))
    )
    (net (code "153") (name "unconnected-(IC1-ADC0_DP3-Pad11)") (class "Default")
      (node (ref "IC1") (pin "11") (pinfunction "ADC0_DP3_11") (pintype "bidirectional"))
    )
    (net (code "154") (name "unconnected-(IC1-EXTAL32-Pad20)") (class "Default")
      (node (ref "IC1") (pin "20") (pinfunction "EXTAL32_20") (pintype "bidirectional"))
    )
    (net (code "155") (name "unconnected-(IC1-VREF_OUT-Pad17)") (class "Default")
      (node (ref "IC1") (pin "17") (pinfunction "VREF_OUT_17") (pintype "bidirectional"))
    )
    (net (code "156") (name "unconnected-(IC1-XTAL32-Pad19)") (class "Default")
      (node (ref "IC1") (pin "19") (pinfunction "XTAL32_19") (pintype "bidirectional"))
    )
    (net (code "157") (name "unconnected-(IC3A-~{QH}-Pad7)") (class "Default")
      (node (ref "IC3") (pin "7") (pinfunction "~{QH}_7") (pintype "output"))
    )
    (net (code "158") (name "unconnected-(J2-ID-Pad4)") (class "Default")
      (node (ref "J2") (pin "4") (pinfunction "ID_4") (pintype "bidirectional"))
    )
    (net (code "159") (name "unconnected-(JP1-EARTH-NORM-PadP$3)") (class "Default")
      (node (ref "JP1") (pin "P$3") (pinfunction "EARTH-NORM_P$3") (pintype "bidirectional"))
    )
    (net (code "160") (name "unconnected-(JP1-RING-NORM-PadP$5)") (class "Default")
      (node (ref "JP1") (pin "P$5") (pinfunction "RING-NORM_P$5") (pintype "bidirectional"))
    )
    (net (code "161") (name "unconnected-(JP1-TIP-NORM-PadP$7)") (class "Default")
      (node (ref "JP1") (pin "P$7") (pinfunction "TIP-NORM_P$7") (pintype "bidirectional"))
    )
    (net (code "162") (name "unconnected-(PORT_MIDI-IN-Pad1)") (class "Default")
      (node (ref "PORT_MIDI-IN") (pin "1") (pinfunction "1_1") (pintype "passive"))
    )
    (net (code "163") (name "unconnected-(PORT_MIDI-IN-Pad2)") (class "Default")
      (node (ref "PORT_MIDI-IN") (pin "2") (pinfunction "2_2") (pintype "passive"))
    )
    (net (code "164") (name "unconnected-(PORT_MIDI-IN-Pad3)") (class "Default")
      (node (ref "PORT_MIDI-IN") (pin "3") (pinfunction "3_3") (pintype "passive"))
    )
    (net (code "165") (name "unconnected-(PORT_MIDI-OUT-Pad1)") (class "Default")
      (node (ref "PORT_MIDI-OUT") (pin "1") (pinfunction "1_1") (pintype "passive"))
    )
    (net (code "166") (name "unconnected-(PORT_MIDI-OUT-Pad3)") (class "Default")
      (node (ref "PORT_MIDI-OUT") (pin "3") (pinfunction "3_3") (pintype "passive"))
    )
    (net (code "167") (name "unconnected-(PORT_MIDI-THROUGH-Pad1)") (class "Default")
      (node (ref "PORT_MIDI-THROUGH") (pin "1") (pinfunction "1_1") (pintype "passive"))
    )
    (net (code "168") (name "unconnected-(PORT_MIDI-THROUGH-Pad3)") (class "Default")
      (node (ref "PORT_MIDI-THROUGH") (pin "3") (pinfunction "3_3") (pintype "passive"))
    )
    (net (code "169") (name "unconnected-(SW2-PadC)") (class "Default")
      (node (ref "SW2") (pin "C") (pinfunction "C_C") (pintype "passive"))
    )
    (net (code "170") (name "unconnected-(SWD1-N{slash}C1-Pad7)") (class "Default")
      (node (ref "SWD1") (pin "7") (pinfunction "N/C1_7") (pintype "bidirectional"))
    )
    (net (code "171") (name "unconnected-(SWD2-GND3-Pad9)") (class "Default")
      (node (ref "SWD2") (pin "9") (pinfunction "GND3_9") (pintype "bidirectional"))
    )
    (net (code "172") (name "unconnected-(SWD2-N{slash}C1-Pad7)") (class "Default")
      (node (ref "SWD2") (pin "7") (pinfunction "N/C1_7") (pintype "bidirectional"))
    )
    (net (code "173") (name "unconnected-(SWD2-N{slash}C2-Pad8)") (class "Default")
      (node (ref "SWD2") (pin "8") (pinfunction "N/C2_8") (pintype "bidirectional"))
    )
    (net (code "174") (name "unconnected-(SWD2-SWO-Pad6)") (class "Default")
      (node (ref "SWD2") (pin "6") (pinfunction "SWO_6") (pintype "bidirectional"))
    )
    (net (code "175") (name "unconnected-(U$1-TE-Pad39)") (class "Default")
      (node (ref "U$1") (pin "39") (pinfunction "TE_39") (pintype "input"))
    )
    (net (code "176") (name "unconnected-(U1-~{1Y}-Pad2)") (class "Default")
      (node (ref "U1") (pin "2") (pinfunction "~{1Y}_2") (pintype "output"))
    )
    (net (code "177") (name "unconnected-(U1-~{2Y}-Pad4)") (class "Default")
      (node (ref "U1") (pin "4") (pinfunction "~{2Y}_4") (pintype "output"))
    )
  )
)
